# controller.net
KiCad netlist of a schematic drawn in EAGLE
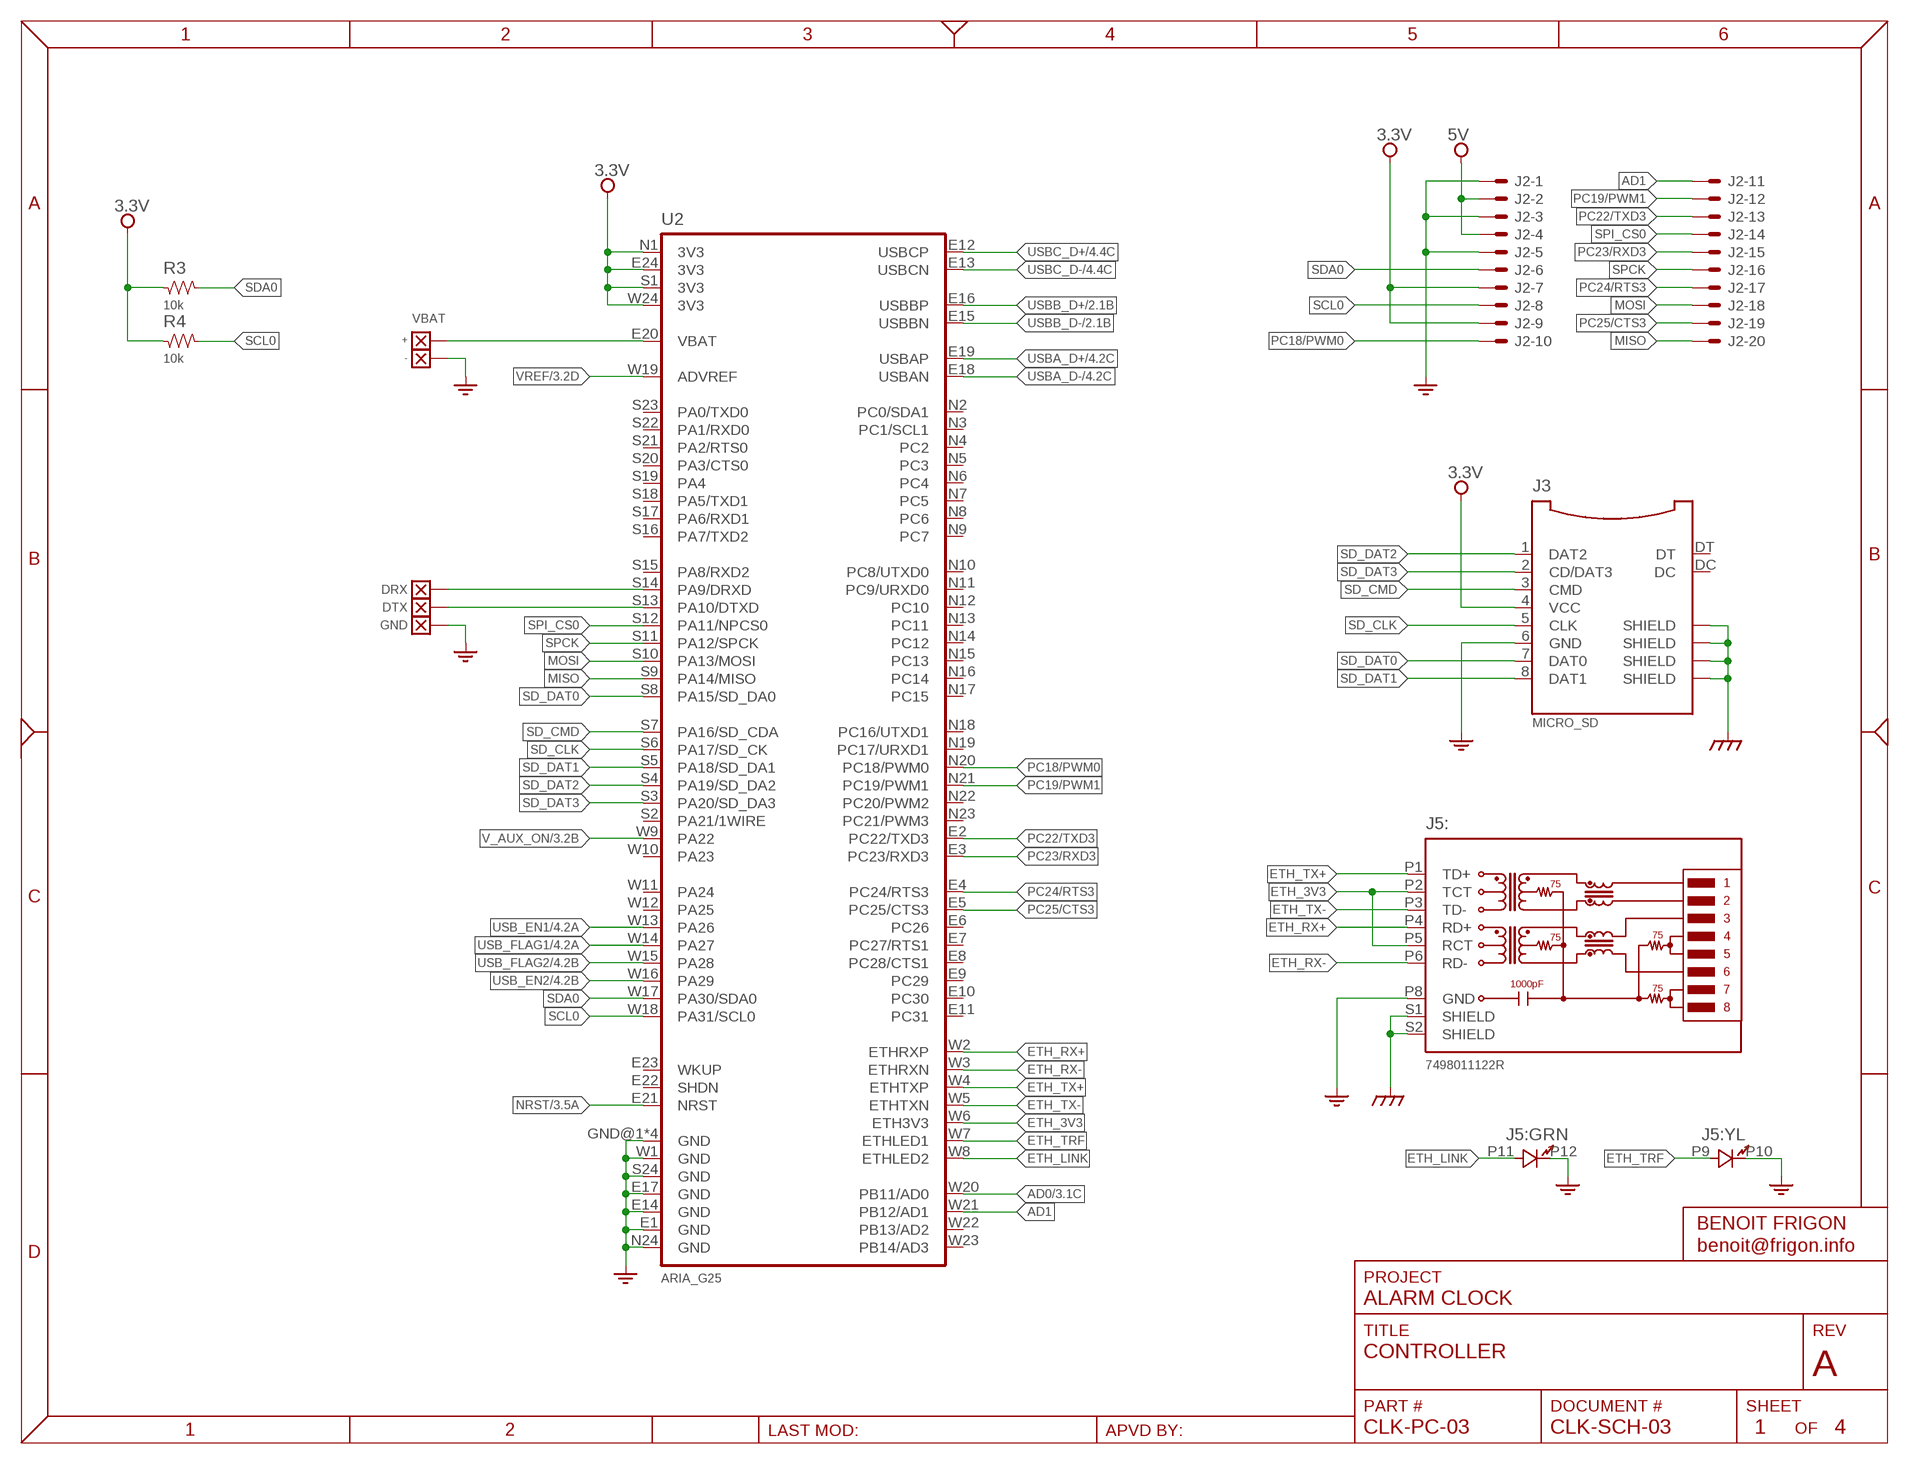
[diagram p0: schematic, sheet 1]
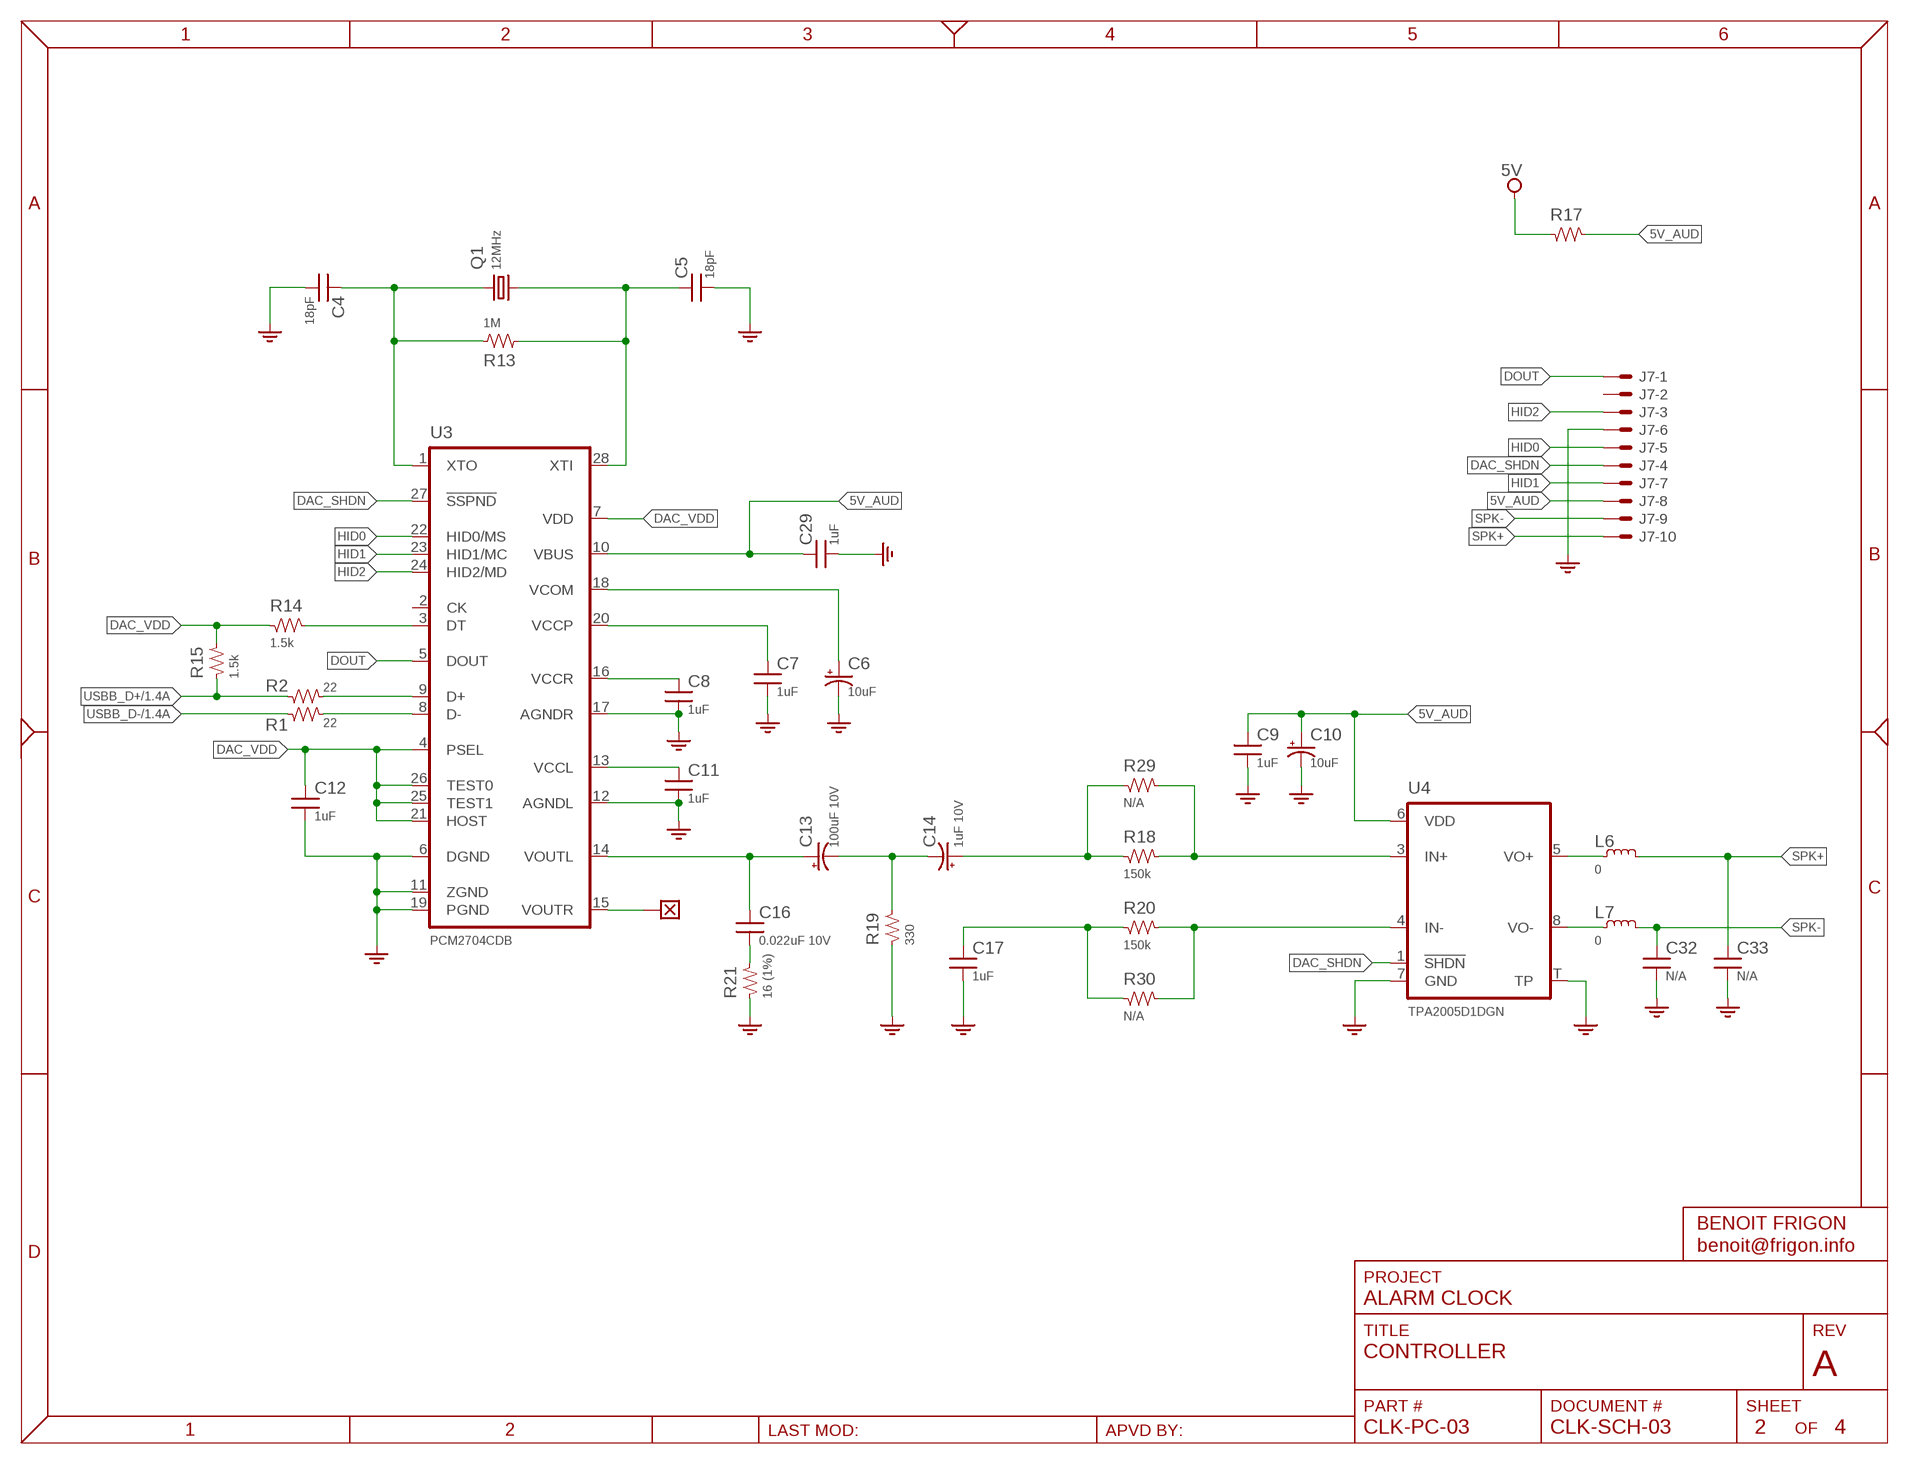
[diagram p1: schematic, sheet 2]
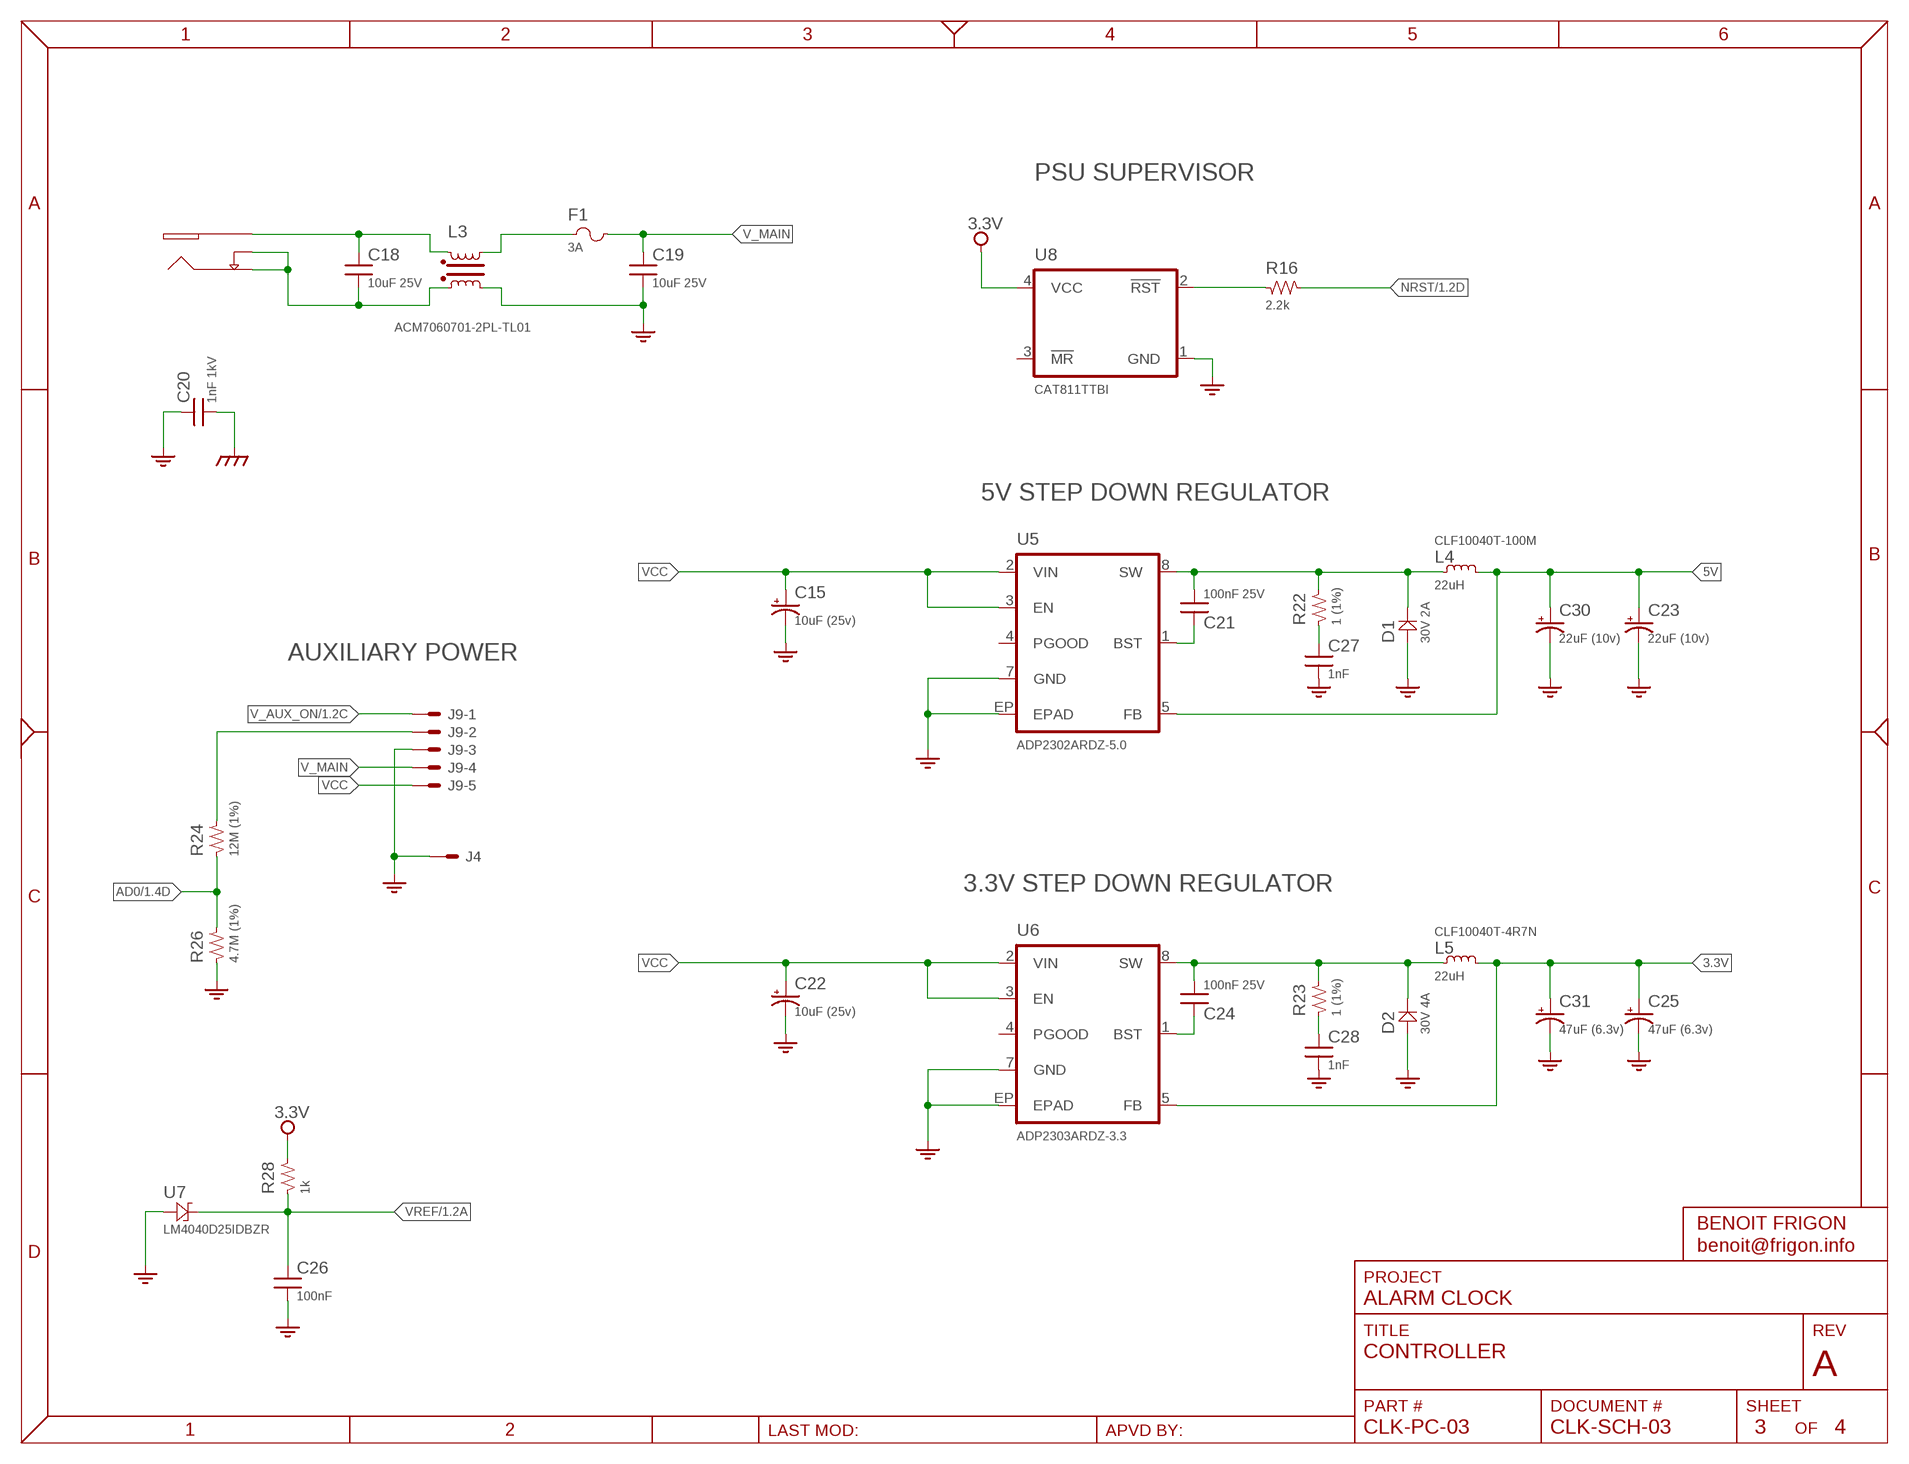
[diagram p2: schematic, sheet 3]
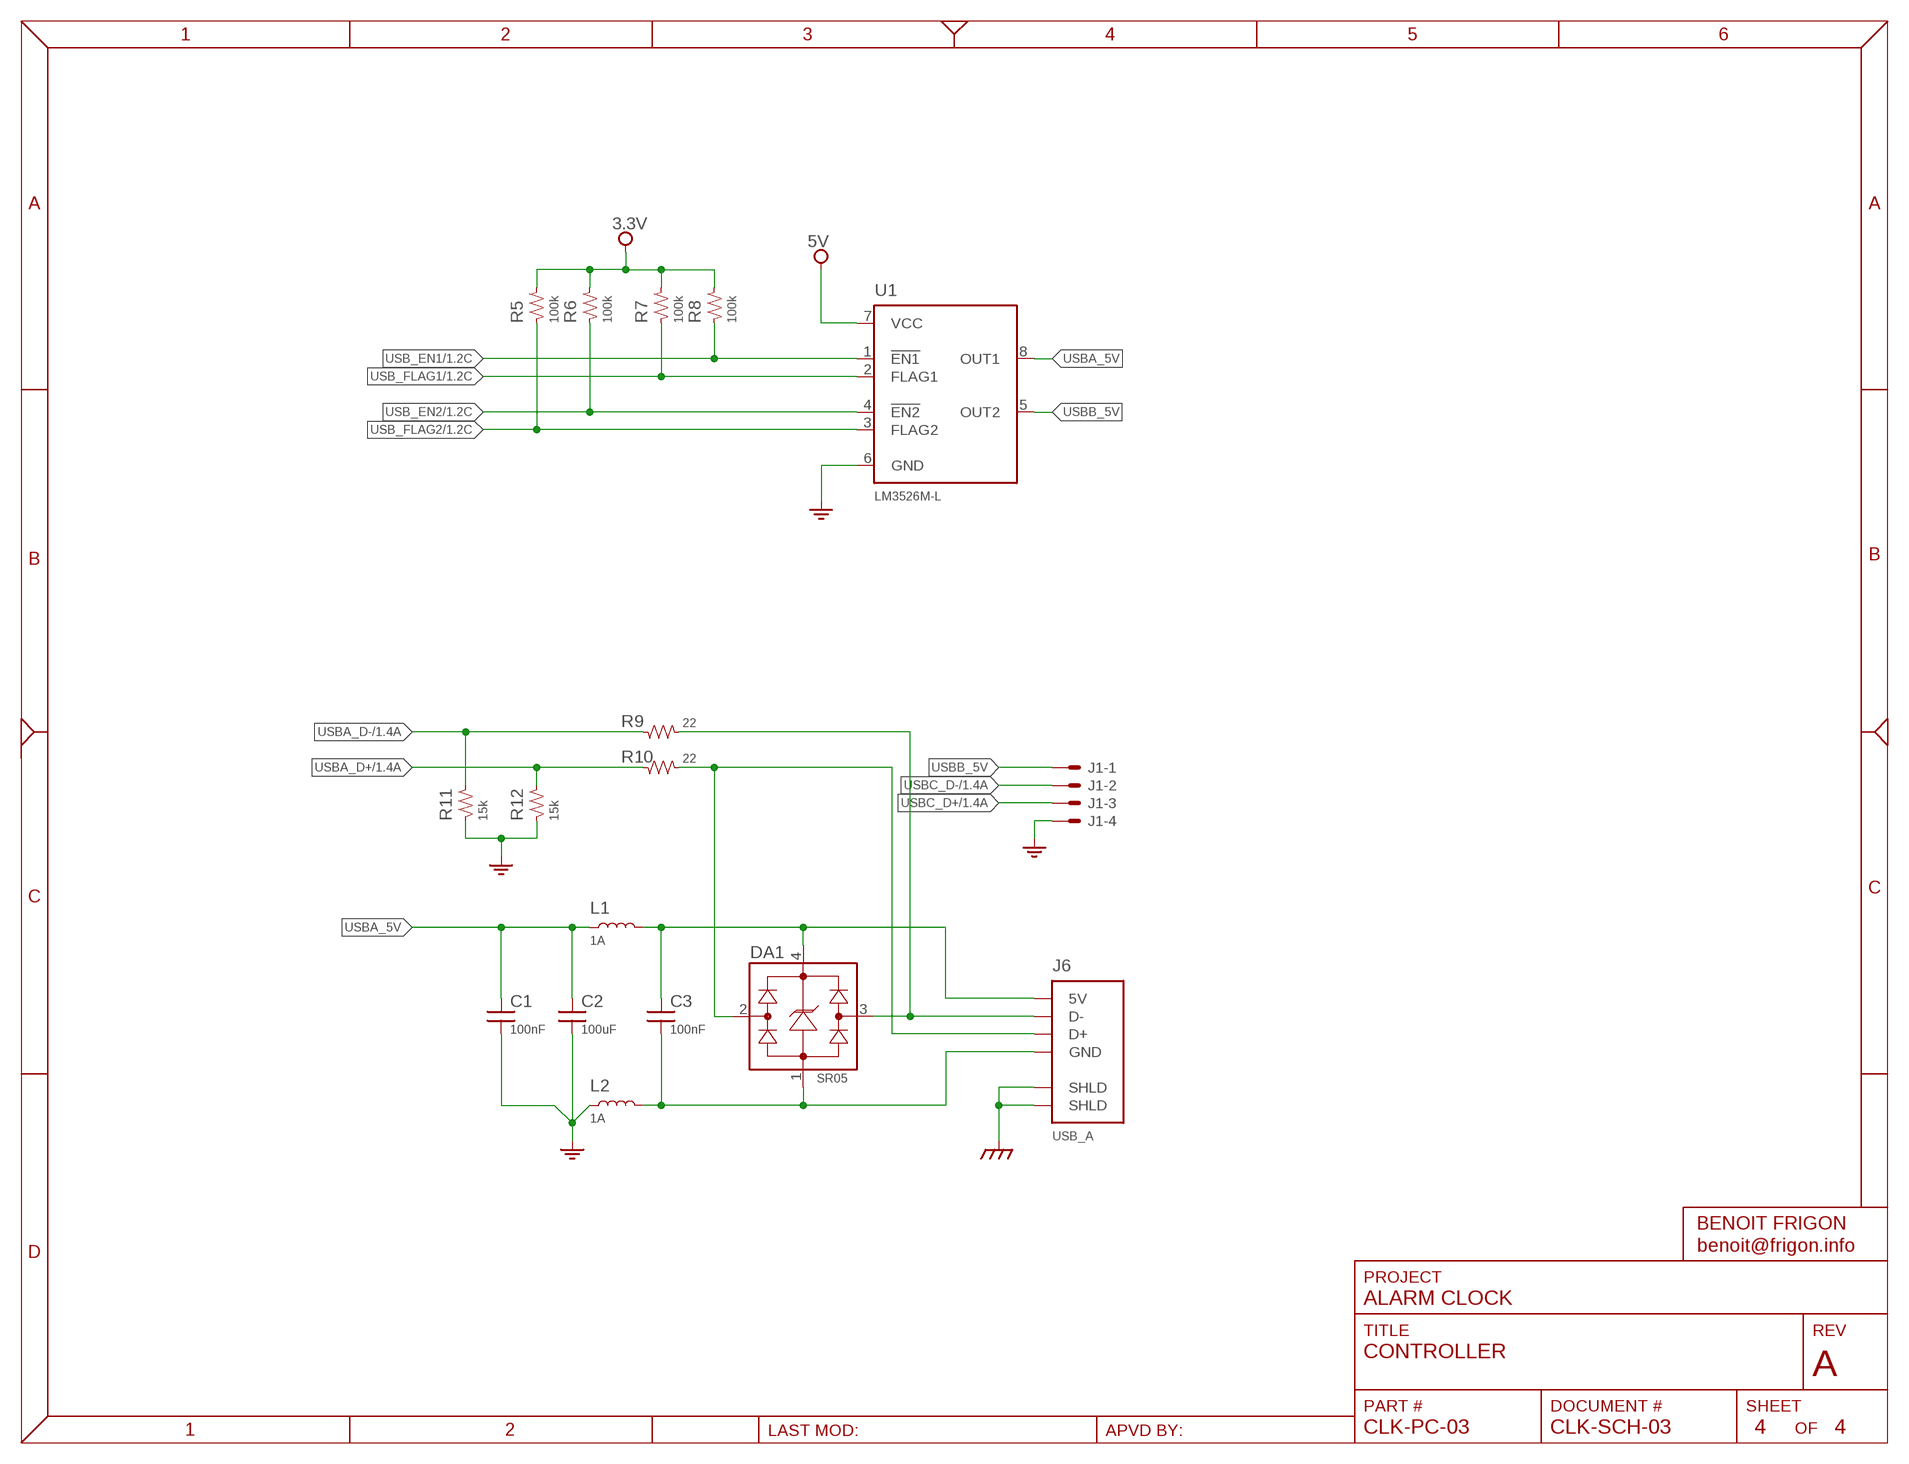
[diagram p3: schematic, sheet 4]

(export (version "E")
  (design (tool "Eeschema 10.0.6"))
  (components
    (comp (ref "C15")
      (value "10uF (25v)")
      (footprint "eagle-import:CAP_S1210")
      (fields (field (name "MFG") "AVX") (field (name "PART_NO") "TPSB106K025R1800"))
      (libsource (lib "eagle-import") (part "CAP-E-?-1210TANT"))
    )
    (comp (ref "C18")
      (value "10uF 25V")
      (footprint "eagle-import:SMD_1206")
      (description "{DESCRIPTION} - SMT 1206 - {value}")
      (fields (field (name "PACKAGE") "SMT 1206"))
      (libsource (lib "eagle-import") (part "CAP-1206"))
    )
    (comp (ref "C19")
      (value "10uF 25V")
      (footprint "eagle-import:SMD_1206")
      (description "{DESCRIPTION} - SMT 1206 - {value}")
      (fields (field (name "PACKAGE") "SMT 1206"))
      (libsource (lib "eagle-import") (part "CAP-1206"))
    )
    (comp (ref "C20")
      (value "1nF 1kV")
      (footprint "eagle-import:SMD_0805")
      (libsource (lib "eagle-import") (part "CAP-0805"))
    )
    (comp (ref "C21")
      (value "100nF 25V")
      (footprint "eagle-import:SMD_0603")
      (libsource (lib "eagle-import") (part "CAP-0603"))
    )
    (comp (ref "C22")
      (value "10uF (25v)")
      (footprint "eagle-import:CAP_S1210")
      (fields (field (name "MFG") "AVX") (field (name "PART_NO") "TPSB106K025R1800"))
      (libsource (lib "eagle-import") (part "CAP-E-?-1210TANT"))
    )
    (comp (ref "C23")
      (value "22uF (10v)")
      (footprint "eagle-import:CAP_S1206")
      (description "Tantalum capacitor - SMT 1206 - {VALUE}")
      (fields (field (name "MFG") "AVX") (field (name "PART_NO") "TPSA226M010R0900"))
      (libsource (lib "eagle-import") (part "CAP-E-?-1206TANT"))
    )
    (comp (ref "C24")
      (value "100nF 25V")
      (footprint "eagle-import:SMD_0603")
      (libsource (lib "eagle-import") (part "CAP-0603"))
    )
    (comp (ref "C25")
      (value "47uF (6.3v)")
      (footprint "eagle-import:CAP_S1206")
      (description "Tantalum capacitor - SMT 1206 - {VALUE}")
      (fields (field (name "MFG") "AVX") (field (name "PART_NO") "TPSA476K006R0800"))
      (libsource (lib "eagle-import") (part "CAP-E-?-1206TANT"))
    )
    (comp (ref "C26")
      (value "100nF")
      (footprint "eagle-import:SMD_0603")
      (libsource (lib "eagle-import") (part "CAP-0603"))
    )
    (comp (ref "C27")
      (value "1nF")
      (footprint "eagle-import:SMD_0805")
      (libsource (lib "eagle-import") (part "CAP-0805"))
    )
    (comp (ref "C28")
      (value "1nF")
      (footprint "eagle-import:SMD_0805")
      (description "{DESCRIPTION} - SMT 0805 - {value}")
      (fields (field (name "PACKAGE") "SMT 0805"))
      (libsource (lib "eagle-import") (part "CAP-0805"))
    )
    (comp (ref "C30")
      (value "22uF (10v)")
      (footprint "eagle-import:CAP_S1206")
      (description "Tantalum capacitor - SMT 1206 - {VALUE}")
      (fields (field (name "MFG") "AVX") (field (name "PART_NO") "TPSA226M010R0900"))
      (libsource (lib "eagle-import") (part "CAP-E-?-1206TANT"))
    )
    (comp (ref "C31")
      (value "47uF (6.3v)")
      (footprint "eagle-import:CAP_S1206")
      (description "Tantalum capacitor - SMT 1206 - {VALUE}")
      (fields (field (name "MFG") "AVX") (field (name "PART_NO") "TPSA476K006R0800"))
      (libsource (lib "eagle-import") (part "CAP-E-?-1206TANT"))
    )
    (comp (ref "D1")
      (value "30V 2A")
      (footprint "eagle-import:DIODE_DO214-AA")
      (libsource (lib "eagle-import") (part "DIODE-DO214-AA"))
    )
    (comp (ref "D2")
      (value "30V 4A")
      (footprint "eagle-import:DIODE_DO214-AA")
      (libsource (lib "eagle-import") (part "DIODE-DO214-AA"))
    )
    (comp (ref "F1")
      (value "3A")
      (footprint "eagle-import:SMD_1206")
      (libsource (lib "eagle-import") (part "FUSE1206"))
    )
    (comp (ref "J4")
      (value "SNG-100-HEADER-01-HDR-V")
      (footprint "eagle-import:HDR_M_1")
      (libsource (lib "eagle-import") (part "SNG-100-HEADER-01-HDR-V"))
    )
    (comp (ref "J8")
      (value "CUI-PJ-013C")
      (footprint "eagle-import:CUI-PJ-013C")
      (libsource (lib "eagle-import") (part "CUI-PJ-013C"))
    )
    (comp (ref "J9")
      (value "SNG-100-HEADER-05-HDR-V")
      (footprint "eagle-import:HDR_M_5")
      (libsource (lib "eagle-import") (part "SNG-100-HEADER-05-HDR-V"))
    )
    (comp (ref "L3")
      (value "ACM7060701-2PL-TL01")
      (footprint "eagle-import:ACM7060")
      (libsource (lib "eagle-import") (part "CHOKE-?ACM7060701-2PL-TL01"))
    )
    (comp (ref "L4")
      (value "22uH")
      (footprint "eagle-import:IND-10X10")
      (fields (field (name "MFG") "TDK") (field (name "PART_NO") "CLF10040T-100M"))
      (libsource (lib "eagle-import") (part "IND?-10X10"))
    )
    (comp (ref "L5")
      (value "22uH")
      (footprint "eagle-import:IND-10X10")
      (fields (field (name "PART_NO") "CLF10040T-4R7N"))
      (libsource (lib "eagle-import") (part "IND?-10X10"))
    )
    (comp (ref "R16")
      (value "2.2k")
      (footprint "eagle-import:SMD_0603")
      (libsource (lib "eagle-import") (part "RES-0603"))
    )
    (comp (ref "R22")
      (value "1 (1%)")
      (footprint "eagle-import:SMD_0805")
      (libsource (lib "eagle-import") (part "RES-0805"))
    )
    (comp (ref "R23")
      (value "1 (1%)")
      (footprint "eagle-import:SMD_0805")
      (description "{DESCRIPTION} - SMT 0805 - {VALUE}")
      (fields (field (name "PACKAGE") "SMT 0805"))
      (libsource (lib "eagle-import") (part "RES-0805"))
    )
    (comp (ref "R24")
      (value "12M (1%)")
      (footprint "eagle-import:SMD_0603")
      (libsource (lib "eagle-import") (part "RES-0603"))
    )
    (comp (ref "R26")
      (value "4.7M (1%)")
      (footprint "eagle-import:SMD_0603")
      (libsource (lib "eagle-import") (part "RES-0603"))
    )
    (comp (ref "R28")
      (value "1k")
      (footprint "eagle-import:SMD_0603")
      (libsource (lib "eagle-import") (part "RES-0603"))
    )
    (comp (ref "U5")
      (value "ADP2302ARDZ-5.0")
      (footprint "eagle-import:SOIC8-EP")
      (description "{DESCRIPTION} - 2A, 5V")
      (fields (field (name "MFG") "Analog Devices"))
      (libsource (lib "eagle-import") (part "ADP230?2ARDZ-5.0"))
    )
    (comp (ref "U6")
      (value "ADP2303ARDZ-3.3")
      (footprint "eagle-import:SOIC8-EP")
      (description "{DESCRIPTION} - 3A, 3.3v")
      (fields (field (name "MFG") "Analog Devices"))
      (libsource (lib "eagle-import") (part "ADP230?3ARDZ-3.3"))
    )
    (comp (ref "U7")
      (value "LM4040D25IDBZR")
      (footprint "eagle-import:SOT23")
      (libsource (lib "eagle-import") (part "TS4040DBZD30I"))
    )
    (comp (ref "U8")
      (value "CAT811TTBI")
      (footprint "eagle-import:SOT143")
      (description "{DESCRIPTION} - 3.08V threshold")
      (fields (field (name "MFG") "ON Semiconductors"))
      (libsource (lib "eagle-import") (part "CAT811?TBIT"))
    )
    (comp (ref "C4")
      (value "18pF")
      (footprint "eagle-import:SMD_0603")
      (description "{DESCRIPTION} - SMT 0603 - {value}")
      (fields (field (name "PACKAGE") "SMT 0603"))
      (libsource (lib "eagle-import") (part "CAP-0603"))
    )
    (comp (ref "C5")
      (value "18pF")
      (footprint "eagle-import:SMD_0603")
      (libsource (lib "eagle-import") (part "CAP-0603"))
    )
    (comp (ref "C6")
      (value "10uF")
      (footprint "eagle-import:CAP_S0805")
      (description "Aluminium capacitor - SMT 0805 - {VALUE}")
      (libsource (lib "eagle-import") (part "CAP-E-?-0805ALUM"))
    )
    (comp (ref "C7")
      (value "1uF")
      (footprint "eagle-import:SMD_0603")
      (libsource (lib "eagle-import") (part "CAP-0603"))
    )
    (comp (ref "C8")
      (value "1uF")
      (footprint "eagle-import:SMD_0603")
      (description "{DESCRIPTION} - SMT 0603 - {value}")
      (fields (field (name "PACKAGE") "SMT 0603"))
      (libsource (lib "eagle-import") (part "CAP-0603"))
    )
    (comp (ref "C9")
      (value "1uF")
      (footprint "eagle-import:SMD_0603")
      (libsource (lib "eagle-import") (part "CAP-0603"))
    )
    (comp (ref "C10")
      (value "10uF")
      (footprint "eagle-import:CAP_S0805")
      (description "Aluminium capacitor - SMT 0805 - {VALUE}")
      (libsource (lib "eagle-import") (part "CAP-E-?-0805ALUM"))
    )
    (comp (ref "C11")
      (value "1uF")
      (footprint "eagle-import:SMD_0603")
      (description "{DESCRIPTION} - SMT 0603 - {value}")
      (fields (field (name "PACKAGE") "SMT 0603"))
      (libsource (lib "eagle-import") (part "CAP-0603"))
    )
    (comp (ref "C12")
      (value "1uF")
      (footprint "eagle-import:SMD_0603")
      (libsource (lib "eagle-import") (part "CAP-0603"))
    )
    (comp (ref "C13")
      (value "100uF 10V")
      (footprint "eagle-import:CAP_S1210")
      (description "Aluminium capacitor - SMT 1210 - {VALUE}")
      (fields (field (name "MFG") "AVX"))
      (libsource (lib "eagle-import") (part "CAP-E-?-1210ALUM"))
    )
    (comp (ref "C14")
      (value "1uF 10V")
      (footprint "eagle-import:CAP_S0805")
      (description "Aluminium capacitor - SMT 0805 - {VALUE}")
      (libsource (lib "eagle-import") (part "CAP-E-?-0805ALUM"))
    )
    (comp (ref "C16")
      (value "0.022uF 10V")
      (footprint "eagle-import:SMD_0603")
      (libsource (lib "eagle-import") (part "CAP-0603"))
    )
    (comp (ref "C17")
      (value "1uF")
      (footprint "eagle-import:SMD_0603")
      (libsource (lib "eagle-import") (part "CAP-0603"))
    )
    (comp (ref "C29")
      (value "1uF")
      (footprint "eagle-import:SMD_0603")
      (libsource (lib "eagle-import") (part "CAP-0603"))
    )
    (comp (ref "C32")
      (value "N/A")
      (footprint "eagle-import:SMD_0603")
      (libsource (lib "eagle-import") (part "CAP-0603"))
    )
    (comp (ref "C33")
      (value "N/A")
      (footprint "eagle-import:SMD_0603")
      (libsource (lib "eagle-import") (part "CAP-0603"))
    )
    (comp (ref "J7")
      (value "DL-1.25MM-HEADER-10")
      (footprint "eagle-import:DF13A-10DP-1.25")
      (libsource (lib "eagle-import") (part "DL-1.25MM-HEADER-10"))
    )
    (comp (ref "L6")
      (value "0")
      (footprint "eagle-import:SMD_0603")
      (description "{DESCRIPTION} - SMT 0603 - {VALUE}")
      (libsource (lib "eagle-import") (part "IND?-0603"))
    )
    (comp (ref "L7")
      (value "0")
      (footprint "eagle-import:SMD_0603")
      (description "{DESCRIPTION} - SMT 0603 - {VALUE}")
      (libsource (lib "eagle-import") (part "IND?-0603"))
    )
    (comp (ref "Q1")
      (value "12MHz")
      (footprint "eagle-import:HC49UP")
      (libsource (lib "eagle-import") (part "XTALHC49UP"))
    )
    (comp (ref "R1")
      (value "22")
      (footprint "eagle-import:SMD_0603")
      (libsource (lib "eagle-import") (part "RES-0603"))
    )
    (comp (ref "R2")
      (value "22")
      (footprint "eagle-import:SMD_0603")
      (libsource (lib "eagle-import") (part "RES-0603"))
    )
    (comp (ref "R13")
      (value "1M")
      (footprint "eagle-import:SMD_0603")
      (libsource (lib "eagle-import") (part "RES-0603"))
    )
    (comp (ref "R14")
      (value "1.5k")
      (footprint "eagle-import:SMD_0603")
      (libsource (lib "eagle-import") (part "RES-0603"))
    )
    (comp (ref "R15")
      (value "1.5k")
      (footprint "eagle-import:SMD_0603")
      (libsource (lib "eagle-import") (part "RES-0603"))
    )
    (comp (ref "R17")
      (value "RES-1206")
      (footprint "eagle-import:SMD_1206")
      (libsource (lib "eagle-import") (part "RES-1206"))
    )
    (comp (ref "R18")
      (value "150k")
      (footprint "eagle-import:SMD_0603")
      (libsource (lib "eagle-import") (part "RES-0603"))
    )
    (comp (ref "R19")
      (value "330")
      (footprint "eagle-import:SMD_0603")
      (libsource (lib "eagle-import") (part "RES-0603"))
    )
    (comp (ref "R20")
      (value "150k")
      (footprint "eagle-import:SMD_0603")
      (description "{DESCRIPTION} - SMT 0603 - {VALUE}")
      (fields (field (name "PACKAGE") "SMT 0603"))
      (libsource (lib "eagle-import") (part "RES-0603"))
    )
    (comp (ref "R21")
      (value "16 (1%)")
      (footprint "eagle-import:SMD_0603")
      (libsource (lib "eagle-import") (part "RES-0603"))
    )
    (comp (ref "R29")
      (value "N/A")
      (footprint "eagle-import:SMD_0603")
      (description "{DESCRIPTION} - SMT 0603 - {VALUE}")
      (fields (field (name "PACKAGE") "SMT 0603"))
      (libsource (lib "eagle-import") (part "RES-0603"))
    )
    (comp (ref "R30")
      (value "N/A")
      (footprint "eagle-import:SMD_0603")
      (description "{DESCRIPTION} - SMT 0603 - {VALUE}")
      (fields (field (name "PACKAGE") "SMT 0603"))
      (libsource (lib "eagle-import") (part "RES-0603"))
    )
    (comp (ref "U3")
      (value "PCM2704CDB")
      (footprint "eagle-import:SSOP28")
      (libsource (lib "eagle-import") (part "PCM2704CDB"))
    )
    (comp (ref "U4")
      (value "TPA2005D1DGN")
      (footprint "eagle-import:PPSOP8")
      (libsource (lib "eagle-import") (part "TPA2005D1?DGN"))
    )
    (comp (ref "W1")
      (value "WIRE-150X75")
      (footprint "eagle-import:WIRE_SMT_150X75")
      (libsource (lib "eagle-import") (part "WIRE-?150X75"))
    )
    (comp (ref "J2")
      (value "DL-1.25MM-HEADER-20")
      (footprint "eagle-import:DF13A-20DP-1.25")
      (libsource (lib "eagle-import") (part "DL-1.25MM-HEADER-20"))
    )
    (comp (ref "J3")
      (value "MICRO_SD")
      (footprint "eagle-import:5027020891")
      (libsource (lib "eagle-import") (part "MICRO_SD"))
    )
    (comp (ref "J5")
      (value "7498011122R")
      (footprint "eagle-import:7498011122R")
      (libsource (lib "eagle-import") (part "7498011122R"))
    )
    (comp (ref "R3")
      (value "10k")
      (footprint "eagle-import:SMD_0603")
      (description "{DESCRIPTION} - SMT 0603 - {VALUE}")
      (fields (field (name "PACKAGE") "SMT 0603"))
      (libsource (lib "eagle-import") (part "RES-0603"))
    )
    (comp (ref "R4")
      (value "10k")
      (footprint "eagle-import:SMD_0603")
      (description "{DESCRIPTION} - SMT 0603 - {VALUE}")
      (fields (field (name "PACKAGE") "SMT 0603"))
      (libsource (lib "eagle-import") (part "RES-0603"))
    )
    (comp (ref "TP1")
      (value "+")
      (footprint "eagle-import:WIRE_SMT_150X75")
      (libsource (lib "eagle-import") (part "WIRE-?150X75"))
    )
    (comp (ref "TP2")
      (value "-")
      (footprint "eagle-import:WIRE_SMT_150X75")
      (libsource (lib "eagle-import") (part "WIRE-?150X75"))
    )
    (comp (ref "U2")
      (value "ARIA_G25")
      (footprint "eagle-import:ARIA_G25")
      (libsource (lib "eagle-import") (part "ARIA_G25"))
    )
    (comp (ref "W2")
      (value "DRX")
      (footprint "eagle-import:WIRE_SMT_150X75")
      (libsource (lib "eagle-import") (part "WIRE-?150X75"))
    )
    (comp (ref "W3")
      (value "DTX")
      (footprint "eagle-import:WIRE_SMT_150X75")
      (libsource (lib "eagle-import") (part "WIRE-?150X75"))
    )
    (comp (ref "W4")
      (value "GND")
      (footprint "eagle-import:WIRE_SMT_150X75")
      (libsource (lib "eagle-import") (part "WIRE-?150X75"))
    )
    (comp (ref "C1")
      (value "100nF")
      (footprint "eagle-import:SMD_0603")
      (libsource (lib "eagle-import") (part "CAP-0603"))
    )
    (comp (ref "C2")
      (value "100uF")
      (footprint "eagle-import:SMD_0805")
      (libsource (lib "eagle-import") (part "CAP-0805"))
    )
    (comp (ref "C3")
      (value "100nF")
      (footprint "eagle-import:SMD_0603")
      (libsource (lib "eagle-import") (part "CAP-0603"))
    )
    (comp (ref "DA1")
      (value "SR05")
      (footprint "eagle-import:SOT143")
      (fields (field (name "MFG") "Semtech"))
      (libsource (lib "eagle-import") (part "SR05"))
    )
    (comp (ref "J1")
      (value "SNG-2MM-HEADER-04-V")
      (footprint "eagle-import:DF3X-4P-2DSA")
      (description "{DESCRIPTION} - Vertical")
      (fields (field (name "MFG") "Hirose Electronic") (field (name "SKU") "DF3A-4P-2DSA"))
      (libsource (lib "eagle-import") (part "SNG-2MM-HEADER-04-V"))
    )
    (comp (ref "J6")
      (value "USB_A")
      (footprint "eagle-import:292303-7")
      (libsource (lib "eagle-import") (part "USB_A"))
    )
    (comp (ref "L1")
      (value "1A")
      (footprint "eagle-import:SMD_0805")
      (libsource (lib "eagle-import") (part "FERRITE"))
    )
    (comp (ref "L2")
      (value "1A")
      (footprint "eagle-import:SMD_0805")
      (description "{DESCRIPTION} - SMT 0805 - {VALUE}")
      (libsource (lib "eagle-import") (part "FERRITE"))
    )
    (comp (ref "R5")
      (value "100k")
      (footprint "eagle-import:SMD_0603")
      (description "{DESCRIPTION} - SMT 0603 - {VALUE}")
      (fields (field (name "PACKAGE") "SMT 0603"))
      (libsource (lib "eagle-import") (part "RES-0603"))
    )
    (comp (ref "R6")
      (value "100k")
      (footprint "eagle-import:SMD_0603")
      (description "{DESCRIPTION} - SMT 0603 - {VALUE}")
      (fields (field (name "PACKAGE") "SMT 0603"))
      (libsource (lib "eagle-import") (part "RES-0603"))
    )
    (comp (ref "R7")
      (value "100k")
      (footprint "eagle-import:SMD_0603")
      (description "{DESCRIPTION} - SMT 0603 - {VALUE}")
      (fields (field (name "PACKAGE") "SMT 0603"))
      (libsource (lib "eagle-import") (part "RES-0603"))
    )
    (comp (ref "R8")
      (value "100k")
      (footprint "eagle-import:SMD_0603")
      (description "{DESCRIPTION} - SMT 0603 - {VALUE}")
      (fields (field (name "PACKAGE") "SMT 0603"))
      (libsource (lib "eagle-import") (part "RES-0603"))
    )
    (comp (ref "R9")
      (value "22")
      (footprint "eagle-import:SMD_0603")
      (description "{DESCRIPTION} - SMT 0603 - {VALUE}")
      (fields (field (name "PACKAGE") "SMT 0603"))
      (libsource (lib "eagle-import") (part "RES-0603"))
    )
    (comp (ref "R10")
      (value "22")
      (footprint "eagle-import:SMD_0603")
      (description "{DESCRIPTION} - SMT 0603 - {VALUE}")
      (fields (field (name "PACKAGE") "SMT 0603"))
      (libsource (lib "eagle-import") (part "RES-0603"))
    )
    (comp (ref "R11")
      (value "15k")
      (footprint "eagle-import:SMD_0603")
      (description "{DESCRIPTION} - SMT 0603 - {VALUE}")
      (fields (field (name "PACKAGE") "SMT 0603"))
      (libsource (lib "eagle-import") (part "RES-0603"))
    )
    (comp (ref "R12")
      (value "15k")
      (footprint "eagle-import:SMD_0603")
      (description "{DESCRIPTION} - SMT 0603 - {VALUE}")
      (fields (field (name "PACKAGE") "SMT 0603"))
      (libsource (lib "eagle-import") (part "RES-0603"))
    )
    (comp (ref "U1")
      (value "LM3526M-L")
      (footprint "eagle-import:SOIC8")
      (fields (field (name "MFG") "National Semiconductors"))
      (libsource (lib "eagle-import") (part "LM3526?-ML"))
    )
  )
  (nets
    (net (code "1") (name "3.3V") (class "Default")
      (node (ref "C25") (pin "+") (pinfunction "+_+") (pintype "passive"))
      (node (ref "C31") (pin "+") (pinfunction "+_+") (pintype "passive"))
      (node (ref "J2") (pin "7") (pinfunction "S_7") (pintype "bidirectional"))
      (node (ref "J2") (pin "9") (pinfunction "S_9") (pintype "bidirectional"))
      (node (ref "J3") (pin "4") (pinfunction "VCC_4") (pintype "power_in"))
      (node (ref "L5") (pin "2") (pinfunction "2_2") (pintype "passive"))
      (node (ref "R28") (pin "2") (pinfunction "2_2") (pintype "passive"))
      (node (ref "R3") (pin "1") (pinfunction "1_1") (pintype "passive"))
      (node (ref "R4") (pin "1") (pinfunction "1_1") (pintype "passive"))
      (node (ref "R5") (pin "2") (pinfunction "2_2") (pintype "passive"))
      (node (ref "R6") (pin "2") (pinfunction "2_2") (pintype "passive"))
      (node (ref "R7") (pin "2") (pinfunction "2_2") (pintype "passive"))
      (node (ref "R8") (pin "2") (pinfunction "2_2") (pintype "passive"))
      (node (ref "U2") (pin "E24") (pinfunction "3V3_E24") (pintype "power_in"))
      (node (ref "U2") (pin "N1") (pinfunction "3V3_N1") (pintype "power_in"))
      (node (ref "U2") (pin "S1") (pinfunction "3V3_S1") (pintype "power_in"))
      (node (ref "U2") (pin "W24") (pinfunction "3V3_W24") (pintype "power_in"))
      (node (ref "U6") (pin "5") (pinfunction "FB_5") (pintype "bidirectional"))
      (node (ref "U8") (pin "4") (pinfunction "VCC_4") (pintype "power_in"))
    )
    (net (code "2") (name "5V") (class "Default")
      (node (ref "C23") (pin "+") (pinfunction "+_+") (pintype "passive"))
      (node (ref "C30") (pin "+") (pinfunction "+_+") (pintype "passive"))
      (node (ref "J2") (pin "2") (pinfunction "S_2") (pintype "bidirectional"))
      (node (ref "J2") (pin "4") (pinfunction "S_4") (pintype "bidirectional"))
      (node (ref "L4") (pin "2") (pinfunction "2_2") (pintype "passive"))
      (node (ref "R17") (pin "1") (pinfunction "1_1") (pintype "passive"))
      (node (ref "U1") (pin "7") (pinfunction "VCC_7") (pintype "bidirectional"))
      (node (ref "U5") (pin "5") (pinfunction "FB_5") (pintype "bidirectional"))
    )
    (net (code "3") (name "5V_AUD") (class "Default")
      (node (ref "C10") (pin "+") (pinfunction "+_+") (pintype "passive"))
      (node (ref "C29") (pin "1") (pinfunction "1_1") (pintype "passive"))
      (node (ref "C9") (pin "1") (pinfunction "1_1") (pintype "passive"))
      (node (ref "J7") (pin "8") (pinfunction "S_8") (pintype "bidirectional"))
      (node (ref "R17") (pin "2") (pinfunction "2_2") (pintype "passive"))
      (node (ref "U3") (pin "10") (pinfunction "VBUS_10") (pintype "bidirectional"))
      (node (ref "U4") (pin "6") (pinfunction "VDD_6") (pintype "bidirectional"))
    )
    (net (code "4") (name "AD0") (class "Default")
      (node (ref "R24") (pin "1") (pinfunction "1_1") (pintype "passive"))
      (node (ref "R26") (pin "2") (pinfunction "2_2") (pintype "passive"))
      (node (ref "U2") (pin "W20") (pinfunction "PB11/AD0_W20") (pintype "bidirectional"))
    )
    (net (code "5") (name "AD1") (class "Default")
      (node (ref "J2") (pin "11") (pinfunction "S_11") (pintype "bidirectional"))
      (node (ref "U2") (pin "W21") (pinfunction "PB12/AD1_W21") (pintype "bidirectional"))
    )
    (net (code "6") (name "DAC_SHDN") (class "Default")
      (node (ref "J7") (pin "4") (pinfunction "S_4") (pintype "bidirectional"))
      (node (ref "U3") (pin "27") (pinfunction "~{SSPND}_27") (pintype "bidirectional"))
      (node (ref "U4") (pin "1") (pinfunction "~{SHDN}_1") (pintype "bidirectional"))
    )
    (net (code "7") (name "DAC_VDD") (class "Default")
      (node (ref "C12") (pin "1") (pinfunction "1_1") (pintype "passive"))
      (node (ref "R14") (pin "1") (pinfunction "1_1") (pintype "passive"))
      (node (ref "R15") (pin "2") (pinfunction "2_2") (pintype "passive"))
      (node (ref "U3") (pin "21") (pinfunction "HOST_21") (pintype "bidirectional"))
      (node (ref "U3") (pin "25") (pinfunction "TEST1_25") (pintype "bidirectional"))
      (node (ref "U3") (pin "26") (pinfunction "TEST0_26") (pintype "bidirectional"))
      (node (ref "U3") (pin "4") (pinfunction "PSEL_4") (pintype "bidirectional"))
      (node (ref "U3") (pin "7") (pinfunction "VDD_7") (pintype "bidirectional"))
    )
    (net (code "8") (name "DOUT") (class "Default")
      (node (ref "J7") (pin "1") (pinfunction "S_1") (pintype "bidirectional"))
      (node (ref "U3") (pin "5") (pinfunction "DOUT_5") (pintype "bidirectional"))
    )
    (net (code "9") (name "EARTH") (class "Default")
      (node (ref "C20") (pin "2") (pinfunction "2_2") (pintype "passive"))
      (node (ref "J3") (pin "SHDL@3") (pinfunction "SHIELD_SHDL@3") (pintype "power_in"))
      (node (ref "J3") (pin "SHLD@1") (pinfunction "SHIELD_SHLD@1") (pintype "power_in"))
      (node (ref "J3") (pin "SHLD@2") (pinfunction "SHIELD_SHLD@2") (pintype "power_in"))
      (node (ref "J3") (pin "SHLD@4") (pinfunction "SHIELD_SHLD@4") (pintype "power_in"))
      (node (ref "J5") (pin "S1") (pinfunction "SHIELD_S1") (pintype "bidirectional"))
      (node (ref "J5") (pin "S2") (pinfunction "SHIELD_S2") (pintype "bidirectional"))
      (node (ref "J6") (pin "SHLD@1") (pinfunction "SHLD_SHLD@1") (pintype "bidirectional"))
      (node (ref "J6") (pin "SHLD@2") (pinfunction "SHLD_SHLD@2") (pintype "bidirectional"))
    )
    (net (code "10") (name "ETH_3V3") (class "Default")
      (node (ref "J5") (pin "P2") (pinfunction "TCT_P2") (pintype "bidirectional"))
      (node (ref "J5") (pin "P5") (pinfunction "RCT_P5") (pintype "bidirectional"))
      (node (ref "U2") (pin "W6") (pinfunction "ETH3V3_W6") (pintype "bidirectional"))
    )
    (net (code "11") (name "ETH_LINK") (class "Default")
      (node (ref "J5") (pin "P11") (pinfunction "A_P11") (pintype "bidirectional"))
      (node (ref "U2") (pin "W8") (pinfunction "ETHLED2_W8") (pintype "bidirectional"))
    )
    (net (code "12") (name "ETH_RX+") (class "Default")
      (node (ref "J5") (pin "P4") (pinfunction "RD+_P4") (pintype "bidirectional"))
      (node (ref "U2") (pin "W2") (pinfunction "ETHRXP_W2") (pintype "bidirectional"))
    )
    (net (code "13") (name "ETH_RX-") (class "Default")
      (node (ref "J5") (pin "P6") (pinfunction "RD-_P6") (pintype "bidirectional"))
      (node (ref "U2") (pin "W3") (pinfunction "ETHRXN_W3") (pintype "bidirectional"))
    )
    (net (code "14") (name "ETH_TRF") (class "Default")
      (node (ref "J5") (pin "P9") (pinfunction "A_P9") (pintype "bidirectional"))
      (node (ref "U2") (pin "W7") (pinfunction "ETHLED1_W7") (pintype "bidirectional"))
    )
    (net (code "15") (name "ETH_TX+") (class "Default")
      (node (ref "J5") (pin "P1") (pinfunction "TD+_P1") (pintype "bidirectional"))
      (node (ref "U2") (pin "W4") (pinfunction "ETHTXP_W4") (pintype "bidirectional"))
    )
    (net (code "16") (name "ETH_TX-") (class "Default")
      (node (ref "J5") (pin "P3") (pinfunction "TD-_P3") (pintype "bidirectional"))
      (node (ref "U2") (pin "W5") (pinfunction "ETHTXN_W5") (pintype "bidirectional"))
    )
    (net (code "17") (name "GND") (class "Default")
      (node (ref "C1") (pin "2") (pinfunction "2_2") (pintype "passive"))
      (node (ref "C10") (pin "-") (pinfunction "-_-") (pintype "passive"))
      (node (ref "C11") (pin "2") (pinfunction "2_2") (pintype "passive"))
      (node (ref "C12") (pin "2") (pinfunction "2_2") (pintype "passive"))
      (node (ref "C15") (pin "-") (pinfunction "-_-") (pintype "passive"))
      (node (ref "C17") (pin "2") (pinfunction "2_2") (pintype "passive"))
      (node (ref "C19") (pin "2") (pinfunction "2_2") (pintype "passive"))
      (node (ref "C2") (pin "2") (pinfunction "2_2") (pintype "passive"))
      (node (ref "C20") (pin "1") (pinfunction "1_1") (pintype "passive"))
      (node (ref "C22") (pin "-") (pinfunction "-_-") (pintype "passive"))
      (node (ref "C23") (pin "-") (pinfunction "-_-") (pintype "passive"))
      (node (ref "C25") (pin "-") (pinfunction "-_-") (pintype "passive"))
      (node (ref "C26") (pin "2") (pinfunction "2_2") (pintype "passive"))
      (node (ref "C27") (pin "2") (pinfunction "2_2") (pintype "passive"))
      (node (ref "C28") (pin "2") (pinfunction "2_2") (pintype "passive"))
      (node (ref "C29") (pin "2") (pinfunction "2_2") (pintype "passive"))
      (node (ref "C30") (pin "-") (pinfunction "-_-") (pintype "passive"))
      (node (ref "C31") (pin "-") (pinfunction "-_-") (pintype "passive"))
      (node (ref "C32") (pin "2") (pinfunction "2_2") (pintype "passive"))
      (node (ref "C33") (pin "2") (pinfunction "2_2") (pintype "passive"))
      (node (ref "C4") (pin "2") (pinfunction "2_2") (pintype "passive"))
      (node (ref "C5") (pin "2") (pinfunction "2_2") (pintype "passive"))
      (node (ref "C6") (pin "-") (pinfunction "-_-") (pintype "passive"))
      (node (ref "C7") (pin "2") (pinfunction "2_2") (pintype "passive"))
      (node (ref "C8") (pin "2") (pinfunction "2_2") (pintype "passive"))
      (node (ref "C9") (pin "2") (pinfunction "2_2") (pintype "passive"))
      (node (ref "D1") (pin "A") (pinfunction "A_A") (pintype "passive"))
      (node (ref "D2") (pin "A") (pinfunction "A_A") (pintype "passive"))
      (node (ref "J1") (pin "4") (pinfunction "S_4") (pintype "bidirectional"))
      (node (ref "J2") (pin "1") (pinfunction "S_1") (pintype "bidirectional"))
      (node (ref "J2") (pin "3") (pinfunction "S_3") (pintype "bidirectional"))
      (node (ref "J2") (pin "5") (pinfunction "S_5") (pintype "bidirectional"))
      (node (ref "J3") (pin "6") (pinfunction "GND_6") (pintype "power_in"))
      (node (ref "J4") (pin "1") (pinfunction "S_1") (pintype "bidirectional"))
      (node (ref "J5") (pin "P10") (pinfunction "K_P10") (pintype "bidirectional"))
      (node (ref "J5") (pin "P12") (pinfunction "K_P12") (pintype "bidirectional"))
      (node (ref "J5") (pin "P8") (pinfunction "GND_P8") (pintype "bidirectional"))
      (node (ref "J7") (pin "6") (pinfunction "S_6") (pintype "bidirectional"))
      (node (ref "J9") (pin "3") (pinfunction "S_3") (pintype "bidirectional"))
      (node (ref "L2") (pin "1") (pinfunction "1_1") (pintype "passive"))
      (node (ref "L3") (pin "OA") (pinfunction "OA_OA") (pintype "passive"))
      (node (ref "R11") (pin "1") (pinfunction "1_1") (pintype "passive"))
      (node (ref "R12") (pin "1") (pinfunction "1_1") (pintype "passive"))
      (node (ref "R19") (pin "1") (pinfunction "1_1") (pintype "passive"))
      (node (ref "R21") (pin "1") (pinfunction "1_1") (pintype "passive"))
      (node (ref "R26") (pin "1") (pinfunction "1_1") (pintype "passive"))
      (node (ref "TP2") (pin "1") (pinfunction "P$1_1") (pintype "bidirectional"))
      (node (ref "U1") (pin "6") (pinfunction "GND_6") (pintype "bidirectional"))
      (node (ref "U2") (pin "E1") (pinfunction "GND_E1") (pintype "power_in"))
      (node (ref "U2") (pin "E14") (pinfunction "GND_E14") (pintype "power_in"))
      (node (ref "U2") (pin "E17") (pinfunction "GND_E17") (pintype "power_in"))
      (node (ref "U2") (pin "GND@1") (pinfunction "GND_GND@1") (pintype "power_in"))
      (node (ref "U2") (pin "GND@2") (pinfunction "GND_GND@2") (pintype "power_in"))
      (node (ref "U2") (pin "GND@3") (pinfunction "GND_GND@3") (pintype "power_in"))
      (node (ref "U2") (pin "GND@4") (pinfunction "GND_GND@4") (pintype "power_in"))
      (node (ref "U2") (pin "N24") (pinfunction "GND_N24") (pintype "power_in"))
      (node (ref "U2") (pin "S24") (pinfunction "GND_S24") (pintype "power_in"))
      (node (ref "U2") (pin "W1") (pinfunction "GND_W1") (pintype "power_in"))
      (node (ref "U3") (pin "11") (pinfunction "ZGND_11") (pintype "bidirectional"))
      (node (ref "U3") (pin "12") (pinfunction "AGNDL_12") (pintype "bidirectional"))
      (node (ref "U3") (pin "17") (pinfunction "AGNDR_17") (pintype "bidirectional"))
      (node (ref "U3") (pin "19") (pinfunction "PGND_19") (pintype "bidirectional"))
      (node (ref "U3") (pin "6") (pinfunction "DGND_6") (pintype "bidirectional"))
      (node (ref "U4") (pin "7") (pinfunction "GND_7") (pintype "bidirectional"))
      (node (ref "U4") (pin "T") (pinfunction "TP_T") (pintype "bidirectional"))
      (node (ref "U5") (pin "7") (pinfunction "GND_7") (pintype "bidirectional"))
      (node (ref "U5") (pin "EP") (pinfunction "EPAD_EP") (pintype "bidirectional"))
      (node (ref "U6") (pin "7") (pinfunction "GND_7") (pintype "bidirectional"))
      (node (ref "U6") (pin "EP") (pinfunction "EPAD_EP") (pintype "bidirectional"))
      (node (ref "U7") (pin "2") (pinfunction "A_2") (pintype "passive"))
      (node (ref "U8") (pin "1") (pinfunction "GND_1") (pintype "power_in"))
      (node (ref "W4") (pin "1") (pinfunction "P$1_1") (pintype "bidirectional"))
    )
    (net (code "18") (name "HID0") (class "Default")
      (node (ref "J7") (pin "5") (pinfunction "S_5") (pintype "bidirectional"))
      (node (ref "U3") (pin "22") (pinfunction "HID0/MS_22") (pintype "bidirectional"))
    )
    (net (code "19") (name "HID1") (class "Default")
      (node (ref "J7") (pin "7") (pinfunction "S_7") (pintype "bidirectional"))
      (node (ref "U3") (pin "23") (pinfunction "HID1/MC_23") (pintype "bidirectional"))
    )
    (net (code "20") (name "HID2") (class "Default")
      (node (ref "J7") (pin "3") (pinfunction "S_3") (pintype "bidirectional"))
      (node (ref "U3") (pin "24") (pinfunction "HID2/MD_24") (pintype "bidirectional"))
    )
    (net (code "21") (name "MISO") (class "Default")
      (node (ref "J2") (pin "20") (pinfunction "S_20") (pintype "bidirectional"))
      (node (ref "U2") (pin "S9") (pinfunction "PA14/MISO_S9") (pintype "bidirectional"))
    )
    (net (code "22") (name "MOSI") (class "Default")
      (node (ref "J2") (pin "18") (pinfunction "S_18") (pintype "bidirectional"))
      (node (ref "U2") (pin "S10") (pinfunction "PA13/MOSI_S10") (pintype "bidirectional"))
    )
    (net (code "23") (name "NRST") (class "Default")
      (node (ref "R16") (pin "2") (pinfunction "2_2") (pintype "passive"))
      (node (ref "U2") (pin "E21") (pinfunction "NRST_E21") (pintype "input"))
    )
    (net (code "24") (name "Net-(C13-Pad-)") (class "Default")
      (node (ref "C13") (pin "-") (pinfunction "-_-") (pintype "passive"))
      (node (ref "C14") (pin "-") (pinfunction "-_-") (pintype "passive"))
      (node (ref "R19") (pin "2") (pinfunction "2_2") (pintype "passive"))
    )
    (net (code "25") (name "Net-(C14-Pad+)") (class "Default")
      (node (ref "C14") (pin "+") (pinfunction "+_+") (pintype "passive"))
      (node (ref "R18") (pin "1") (pinfunction "1_1") (pintype "passive"))
      (node (ref "R29") (pin "1") (pinfunction "1_1") (pintype "passive"))
    )
    (net (code "26") (name "Net-(C16-Pad2)") (class "Default")
      (node (ref "C16") (pin "2") (pinfunction "2_2") (pintype "passive"))
      (node (ref "R21") (pin "2") (pinfunction "2_2") (pintype "passive"))
    )
    (net (code "27") (name "Net-(C17-Pad1)") (class "Default")
      (node (ref "C17") (pin "1") (pinfunction "1_1") (pintype "passive"))
      (node (ref "R20") (pin "1") (pinfunction "1_1") (pintype "passive"))
      (node (ref "R30") (pin "1") (pinfunction "1_1") (pintype "passive"))
    )
    (net (code "28") (name "Net-(C27-Pad1)") (class "Default")
      (node (ref "C27") (pin "1") (pinfunction "1_1") (pintype "passive"))
      (node (ref "R22") (pin "1") (pinfunction "1_1") (pintype "passive"))
    )
    (net (code "29") (name "Net-(C28-Pad1)") (class "Default")
      (node (ref "C28") (pin "1") (pinfunction "1_1") (pintype "passive"))
      (node (ref "R23") (pin "1") (pinfunction "1_1") (pintype "passive"))
    )
    (net (code "30") (name "Net-(F1-Pad1)") (class "Default")
      (node (ref "F1") (pin "1") (pinfunction "1_1") (pintype "passive"))
      (node (ref "L3") (pin "OB") (pinfunction "OB_OB") (pintype "passive"))
    )
    (net (code "31") (name "Net-(J6-5V)") (class "Default")
      (node (ref "C3") (pin "1") (pinfunction "1_1") (pintype "passive"))
      (node (ref "DA1") (pin "4") (pinfunction "4_4") (pintype "passive"))
      (node (ref "J6") (pin "1") (pinfunction "5V_1") (pintype "bidirectional"))
      (node (ref "L1") (pin "2") (pinfunction "2_2") (pintype "passive"))
    )
    (net (code "32") (name "Net-(J6-D+)") (class "Default")
      (node (ref "DA1") (pin "2") (pinfunction "2_2") (pintype "passive"))
      (node (ref "J6") (pin "3") (pinfunction "D+_3") (pintype "bidirectional"))
      (node (ref "R10") (pin "2") (pinfunction "2_2") (pintype "passive"))
    )
    (net (code "33") (name "Net-(J6-D-)") (class "Default")
      (node (ref "DA1") (pin "3") (pinfunction "3_3") (pintype "passive"))
      (node (ref "J6") (pin "2") (pinfunction "D-_2") (pintype "bidirectional"))
      (node (ref "R9") (pin "2") (pinfunction "2_2") (pintype "passive"))
    )
    (net (code "34") (name "Net-(J6-GND)") (class "Default")
      (node (ref "C3") (pin "2") (pinfunction "2_2") (pintype "passive"))
      (node (ref "DA1") (pin "1") (pinfunction "1_1") (pintype "passive"))
      (node (ref "J6") (pin "4") (pinfunction "GND_4") (pintype "bidirectional"))
      (node (ref "L2") (pin "2") (pinfunction "2_2") (pintype "passive"))
    )
    (net (code "35") (name "Net-(J8-GND)") (class "Default")
      (node (ref "C18") (pin "2") (pinfunction "2_2") (pintype "passive"))
      (node (ref "J8") (pin "2") (pinfunction "GND_2") (pintype "bidirectional"))
      (node (ref "J8") (pin "3") (pinfunction "SW_3") (pintype "bidirectional"))
      (node (ref "L3") (pin "IA") (pinfunction "IA_IA") (pintype "passive"))
    )
    (net (code "36") (name "Net-(J8-V+)") (class "Default")
      (node (ref "C18") (pin "1") (pinfunction "1_1") (pintype "passive"))
      (node (ref "J8") (pin "1") (pinfunction "V+_1") (pintype "bidirectional"))
      (node (ref "L3") (pin "IB") (pinfunction "IB_IB") (pintype "passive"))
    )
    (net (code "37") (name "Net-(J9B-S)") (class "Default")
      (node (ref "J9") (pin "2") (pinfunction "S_2") (pintype "bidirectional"))
      (node (ref "R24") (pin "2") (pinfunction "2_2") (pintype "passive"))
    )
    (net (code "38") (name "Net-(TP1-P$1)") (class "Default")
      (node (ref "TP1") (pin "1") (pinfunction "P$1_1") (pintype "bidirectional"))
      (node (ref "U2") (pin "E20") (pinfunction "VBAT_E20") (pintype "power_in"))
    )
    (net (code "39") (name "Net-(U2-PA9{slash}DRXD)") (class "Default")
      (node (ref "U2") (pin "S14") (pinfunction "PA9/DRXD_S14") (pintype "bidirectional"))
      (node (ref "W2") (pin "1") (pinfunction "P$1_1") (pintype "bidirectional"))
    )
    (net (code "40") (name "Net-(U2-PA10{slash}DTXD)") (class "Default")
      (node (ref "U2") (pin "S13") (pinfunction "PA10/DTXD_S13") (pintype "bidirectional"))
      (node (ref "W3") (pin "1") (pinfunction "P$1_1") (pintype "bidirectional"))
    )
    (net (code "41") (name "Net-(U3-D+)") (class "Default")
      (node (ref "R2") (pin "2") (pinfunction "2_2") (pintype "passive"))
      (node (ref "U3") (pin "9") (pinfunction "D+_9") (pintype "bidirectional"))
    )
    (net (code "42") (name "Net-(U3-D-)") (class "Default")
      (node (ref "R1") (pin "2") (pinfunction "2_2") (pintype "passive"))
      (node (ref "U3") (pin "8") (pinfunction "D-_8") (pintype "bidirectional"))
    )
    (net (code "43") (name "Net-(U3-DT)") (class "Default")
      (node (ref "R14") (pin "2") (pinfunction "2_2") (pintype "passive"))
      (node (ref "U3") (pin "3") (pinfunction "DT_3") (pintype "bidirectional"))
    )
    (net (code "44") (name "Net-(U3-VCCL)") (class "Default")
      (node (ref "C11") (pin "1") (pinfunction "1_1") (pintype "passive"))
      (node (ref "U3") (pin "13") (pinfunction "VCCL_13") (pintype "bidirectional"))
    )
    (net (code "45") (name "Net-(U3-VCCP)") (class "Default")
      (node (ref "C7") (pin "1") (pinfunction "1_1") (pintype "passive"))
      (node (ref "U3") (pin "20") (pinfunction "VCCP_20") (pintype "bidirectional"))
    )
    (net (code "46") (name "Net-(U3-VCCR)") (class "Default")
      (node (ref "C8") (pin "1") (pinfunction "1_1") (pintype "passive"))
      (node (ref "U3") (pin "16") (pinfunction "VCCR_16") (pintype "bidirectional"))
    )
    (net (code "47") (name "Net-(U3-VCOM)") (class "Default")
      (node (ref "C6") (pin "+") (pinfunction "+_+") (pintype "passive"))
      (node (ref "U3") (pin "18") (pinfunction "VCOM_18") (pintype "bidirectional"))
    )
    (net (code "48") (name "Net-(U3-VOUTL)") (class "Default")
      (node (ref "C13") (pin "+") (pinfunction "+_+") (pintype "passive"))
      (node (ref "C16") (pin "1") (pinfunction "1_1") (pintype "passive"))
      (node (ref "U3") (pin "14") (pinfunction "VOUTL_14") (pintype "bidirectional"))
    )
    (net (code "49") (name "Net-(U3-VOUTR)") (class "Default")
      (node (ref "U3") (pin "15") (pinfunction "VOUTR_15") (pintype "bidirectional"))
      (node (ref "W1") (pin "1") (pinfunction "P$1_1") (pintype "bidirectional"))
    )
    (net (code "50") (name "Net-(U3-XTI)") (class "Default")
      (node (ref "C5") (pin "1") (pinfunction "1_1") (pintype "passive"))
      (node (ref "Q1") (pin "2") (pinfunction "2_2") (pintype "passive"))
      (node (ref "R13") (pin "2") (pinfunction "2_2") (pintype "passive"))
      (node (ref "U3") (pin "28") (pinfunction "XTI_28") (pintype "bidirectional"))
    )
    (net (code "51") (name "Net-(U3-XTO)") (class "Default")
      (node (ref "C4") (pin "1") (pinfunction "1_1") (pintype "passive"))
      (node (ref "Q1") (pin "1") (pinfunction "1_1") (pintype "passive"))
      (node (ref "R13") (pin "1") (pinfunction "1_1") (pintype "passive"))
      (node (ref "U3") (pin "1") (pinfunction "XTO_1") (pintype "bidirectional"))
    )
    (net (code "52") (name "Net-(U4-IN+)") (class "Default")
      (node (ref "R18") (pin "2") (pinfunction "2_2") (pintype "passive"))
      (node (ref "R29") (pin "2") (pinfunction "2_2") (pintype "passive"))
      (node (ref "U4") (pin "3") (pinfunction "IN+_3") (pintype "bidirectional"))
    )
    (net (code "53") (name "Net-(U4-IN-)") (class "Default")
      (node (ref "R20") (pin "2") (pinfunction "2_2") (pintype "passive"))
      (node (ref "R30") (pin "2") (pinfunction "2_2") (pintype "passive"))
      (node (ref "U4") (pin "4") (pinfunction "IN-_4") (pintype "bidirectional"))
    )
    (net (code "54") (name "Net-(U4-VO+)") (class "Default")
      (node (ref "L6") (pin "1") (pinfunction "1_1") (pintype "passive"))
      (node (ref "U4") (pin "5") (pinfunction "VO+_5") (pintype "bidirectional"))
    )
    (net (code "55") (name "Net-(U4-VO-)") (class "Default")
      (node (ref "L7") (pin "1") (pinfunction "1_1") (pintype "passive"))
      (node (ref "U4") (pin "8") (pinfunction "VO-_8") (pintype "bidirectional"))
    )
    (net (code "56") (name "Net-(U5-BST)") (class "Default")
      (node (ref "C21") (pin "1") (pinfunction "1_1") (pintype "passive"))
      (node (ref "U5") (pin "1") (pinfunction "BST_1") (pintype "bidirectional"))
    )
    (net (code "57") (name "Net-(U5-SW)") (class "Default")
      (node (ref "C21") (pin "2") (pinfunction "2_2") (pintype "passive"))
      (node (ref "D1") (pin "K") (pinfunction "K_K") (pintype "passive"))
      (node (ref "L4") (pin "1") (pinfunction "1_1") (pintype "passive"))
      (node (ref "R22") (pin "2") (pinfunction "2_2") (pintype "passive"))
      (node (ref "U5") (pin "8") (pinfunction "SW_8") (pintype "bidirectional"))
    )
    (net (code "58") (name "Net-(U6-BST)") (class "Default")
      (node (ref "C24") (pin "1") (pinfunction "1_1") (pintype "passive"))
      (node (ref "U6") (pin "1") (pinfunction "BST_1") (pintype "bidirectional"))
    )
    (net (code "59") (name "Net-(U6-SW)") (class "Default")
      (node (ref "C24") (pin "2") (pinfunction "2_2") (pintype "passive"))
      (node (ref "D2") (pin "K") (pinfunction "K_K") (pintype "passive"))
      (node (ref "L5") (pin "1") (pinfunction "1_1") (pintype "passive"))
      (node (ref "R23") (pin "2") (pinfunction "2_2") (pintype "passive"))
      (node (ref "U6") (pin "8") (pinfunction "SW_8") (pintype "bidirectional"))
    )
    (net (code "60") (name "Net-(U8-~{RST})") (class "Default")
      (node (ref "R16") (pin "1") (pinfunction "1_1") (pintype "passive"))
      (node (ref "U8") (pin "2") (pinfunction "~{RST}_2") (pintype "open_collector"))
    )
    (net (code "61") (name "PC18{slash}PWM0") (class "Default")
      (node (ref "J2") (pin "10") (pinfunction "S_10") (pintype "bidirectional"))
      (node (ref "U2") (pin "N20") (pinfunction "PC18/PWM0_N20") (pintype "bidirectional"))
    )
    (net (code "62") (name "PC19{slash}PWM1") (class "Default")
      (node (ref "J2") (pin "12") (pinfunction "S_12") (pintype "bidirectional"))
      (node (ref "U2") (pin "N21") (pinfunction "PC19/PWM1_N21") (pintype "bidirectional"))
    )
    (net (code "63") (name "PC22{slash}TXD3") (class "Default")
      (node (ref "J2") (pin "13") (pinfunction "S_13") (pintype "bidirectional"))
      (node (ref "U2") (pin "E2") (pinfunction "PC22/TXD3_E2") (pintype "bidirectional"))
    )
    (net (code "64") (name "PC23{slash}RXD3") (class "Default")
      (node (ref "J2") (pin "15") (pinfunction "S_15") (pintype "bidirectional"))
      (node (ref "U2") (pin "E3") (pinfunction "PC23/RXD3_E3") (pintype "bidirectional"))
    )
    (net (code "65") (name "PC24{slash}RTS3") (class "Default")
      (node (ref "J2") (pin "17") (pinfunction "S_17") (pintype "bidirectional"))
      (node (ref "U2") (pin "E4") (pinfunction "PC24/RTS3_E4") (pintype "bidirectional"))
    )
    (net (code "66") (name "PC25{slash}CTS3") (class "Default")
      (node (ref "J2") (pin "19") (pinfunction "S_19") (pintype "bidirectional"))
      (node (ref "U2") (pin "E5") (pinfunction "PC25/CTS3_E5") (pintype "bidirectional"))
    )
    (net (code "67") (name "SCL0") (class "Default")
      (node (ref "J2") (pin "8") (pinfunction "S_8") (pintype "bidirectional"))
      (node (ref "R4") (pin "2") (pinfunction "2_2") (pintype "passive"))
      (node (ref "U2") (pin "W18") (pinfunction "PA31/SCL0_W18") (pintype "bidirectional"))
    )
    (net (code "68") (name "SDA0") (class "Default")
      (node (ref "J2") (pin "6") (pinfunction "S_6") (pintype "bidirectional"))
      (node (ref "R3") (pin "2") (pinfunction "2_2") (pintype "passive"))
      (node (ref "U2") (pin "W17") (pinfunction "PA30/SDA0_W17") (pintype "bidirectional"))
    )
    (net (code "69") (name "SD_CLK") (class "Default")
      (node (ref "J3") (pin "5") (pinfunction "CLK_5") (pintype "input"))
      (node (ref "U2") (pin "S6") (pinfunction "PA17/SD_CK_S6") (pintype "bidirectional"))
    )
    (net (code "70") (name "SD_CMD") (class "Default")
      (node (ref "J3") (pin "3") (pinfunction "CMD_3") (pintype "input"))
      (node (ref "U2") (pin "S7") (pinfunction "PA16/SD_CDA_S7") (pintype "bidirectional"))
    )
    (net (code "71") (name "SD_DAT0") (class "Default")
      (node (ref "J3") (pin "7") (pinfunction "DAT0_7") (pintype "bidirectional"))
      (node (ref "U2") (pin "S8") (pinfunction "PA15/SD_DA0_S8") (pintype "bidirectional"))
    )
    (net (code "72") (name "SD_DAT1") (class "Default")
      (node (ref "J3") (pin "8") (pinfunction "DAT1_8") (pintype "bidirectional"))
      (node (ref "U2") (pin "S5") (pinfunction "PA18/SD_DA1_S5") (pintype "bidirectional"))
    )
    (net (code "73") (name "SD_DAT2") (class "Default")
      (node (ref "J3") (pin "1") (pinfunction "DAT2_1") (pintype "bidirectional"))
      (node (ref "U2") (pin "S4") (pinfunction "PA19/SD_DA2_S4") (pintype "bidirectional"))
    )
    (net (code "74") (name "SD_DAT3") (class "Default")
      (node (ref "J3") (pin "2") (pinfunction "CD/DAT3_2") (pintype "bidirectional"))
      (node (ref "U2") (pin "S3") (pinfunction "PA20/SD_DA3_S3") (pintype "bidirectional"))
    )
    (net (code "75") (name "SPCK") (class "Default")
      (node (ref "J2") (pin "16") (pinfunction "S_16") (pintype "bidirectional"))
      (node (ref "U2") (pin "S11") (pinfunction "PA12/SPCK_S11") (pintype "bidirectional"))
    )
    (net (code "76") (name "SPI_CS0") (class "Default")
      (node (ref "J2") (pin "14") (pinfunction "S_14") (pintype "bidirectional"))
      (node (ref "U2") (pin "S12") (pinfunction "PA11/NPCS0_S12") (pintype "bidirectional"))
    )
    (net (code "77") (name "SPK+") (class "Default")
      (node (ref "C33") (pin "1") (pinfunction "1_1") (pintype "passive"))
      (node (ref "J7") (pin "10") (pinfunction "S_10") (pintype "bidirectional"))
      (node (ref "L6") (pin "2") (pinfunction "2_2") (pintype "passive"))
    )
    (net (code "78") (name "SPK-") (class "Default")
      (node (ref "C32") (pin "1") (pinfunction "1_1") (pintype "passive"))
      (node (ref "J7") (pin "9") (pinfunction "S_9") (pintype "bidirectional"))
      (node (ref "L7") (pin "2") (pinfunction "2_2") (pintype "passive"))
    )
    (net (code "79") (name "USBA_5V") (class "Default")
      (node (ref "C1") (pin "1") (pinfunction "1_1") (pintype "passive"))
      (node (ref "C2") (pin "1") (pinfunction "1_1") (pintype "passive"))
      (node (ref "L1") (pin "1") (pinfunction "1_1") (pintype "passive"))
      (node (ref "U1") (pin "8") (pinfunction "OUT1_8") (pintype "power_in"))
    )
    (net (code "80") (name "USBA_D+") (class "Default")
      (node (ref "R10") (pin "1") (pinfunction "1_1") (pintype "passive"))
      (node (ref "R12") (pin "2") (pinfunction "2_2") (pintype "passive"))
      (node (ref "U2") (pin "E19") (pinfunction "USBAP_E19") (pintype "bidirectional"))
    )
    (net (code "81") (name "USBA_D-") (class "Default")
      (node (ref "R11") (pin "2") (pinfunction "2_2") (pintype "passive"))
      (node (ref "R9") (pin "1") (pinfunction "1_1") (pintype "passive"))
      (node (ref "U2") (pin "E18") (pinfunction "USBAN_E18") (pintype "bidirectional"))
    )
    (net (code "82") (name "USBB_5V") (class "Default")
      (node (ref "J1") (pin "1") (pinfunction "S_1") (pintype "bidirectional"))
      (node (ref "U1") (pin "5") (pinfunction "OUT2_5") (pintype "power_in"))
    )
    (net (code "83") (name "USBB_D+") (class "Default")
      (node (ref "R15") (pin "1") (pinfunction "1_1") (pintype "passive"))
      (node (ref "R2") (pin "1") (pinfunction "1_1") (pintype "passive"))
      (node (ref "U2") (pin "E16") (pinfunction "USBBP_E16") (pintype "bidirectional"))
    )
    (net (code "84") (name "USBB_D-") (class "Default")
      (node (ref "R1") (pin "1") (pinfunction "1_1") (pintype "passive"))
      (node (ref "U2") (pin "E15") (pinfunction "USBBN_E15") (pintype "bidirectional"))
    )
    (net (code "85") (name "USBC_D+") (class "Default")
      (node (ref "J1") (pin "3") (pinfunction "S_3") (pintype "bidirectional"))
      (node (ref "U2") (pin "E12") (pinfunction "USBCP_E12") (pintype "bidirectional"))
    )
    (net (code "86") (name "USBC_D-") (class "Default")
      (node (ref "J1") (pin "2") (pinfunction "S_2") (pintype "bidirectional"))
      (node (ref "U2") (pin "E13") (pinfunction "USBCN_E13") (pintype "bidirectional"))
    )
    (net (code "87") (name "USB_EN1") (class "Default")
      (node (ref "R8") (pin "1") (pinfunction "1_1") (pintype "passive"))
      (node (ref "U1") (pin "1") (pinfunction "~{EN1}_1") (pintype "input"))
      (node (ref "U2") (pin "W13") (pinfunction "PA26_W13") (pintype "bidirectional"))
    )
    (net (code "88") (name "USB_EN2") (class "Default")
      (node (ref "R6") (pin "1") (pinfunction "1_1") (pintype "passive"))
      (node (ref "U1") (pin "4") (pinfunction "~{EN2}_4") (pintype "input"))
      (node (ref "U2") (pin "W16") (pinfunction "PA29_W16") (pintype "bidirectional"))
    )
    (net (code "89") (name "USB_FLAG1") (class "Default")
      (node (ref "R7") (pin "1") (pinfunction "1_1") (pintype "passive"))
      (node (ref "U1") (pin "2") (pinfunction "FLAG1_2") (pintype "output"))
      (node (ref "U2") (pin "W14") (pinfunction "PA27_W14") (pintype "bidirectional"))
    )
    (net (code "90") (name "USB_FLAG2") (class "Default")
      (node (ref "R5") (pin "1") (pinfunction "1_1") (pintype "passive"))
      (node (ref "U1") (pin "3") (pinfunction "FLAG2_3") (pintype "output"))
      (node (ref "U2") (pin "W15") (pinfunction "PA28_W15") (pintype "bidirectional"))
    )
    (net (code "91") (name "VCC") (class "Default")
      (node (ref "C15") (pin "+") (pinfunction "+_+") (pintype "passive"))
      (node (ref "C22") (pin "+") (pinfunction "+_+") (pintype "passive"))
      (node (ref "J9") (pin "5") (pinfunction "S_5") (pintype "bidirectional"))
      (node (ref "U5") (pin "2") (pinfunction "VIN_2") (pintype "bidirectional"))
      (node (ref "U5") (pin "3") (pinfunction "EN_3") (pintype "bidirectional"))
      (node (ref "U6") (pin "2") (pinfunction "VIN_2") (pintype "bidirectional"))
      (node (ref "U6") (pin "3") (pinfunction "EN_3") (pintype "bidirectional"))
    )
    (net (code "92") (name "VREF") (class "Default")
      (node (ref "C26") (pin "1") (pinfunction "1_1") (pintype "passive"))
      (node (ref "R28") (pin "1") (pinfunction "1_1") (pintype "passive"))
      (node (ref "U2") (pin "W19") (pinfunction "ADVREF_W19") (pintype "bidirectional"))
      (node (ref "U7") (pin "1") (pinfunction "K_1") (pintype "passive"))
    )
    (net (code "93") (name "V_AUX_ON") (class "Default")
      (node (ref "J9") (pin "1") (pinfunction "S_1") (pintype "bidirectional"))
      (node (ref "U2") (pin "W9") (pinfunction "PA22_W9") (pintype "bidirectional"))
    )
    (net (code "94") (name "V_MAIN") (class "Default")
      (node (ref "C19") (pin "1") (pinfunction "1_1") (pintype "passive"))
      (node (ref "F1") (pin "2") (pinfunction "2_2") (pintype "passive"))
      (node (ref "J9") (pin "4") (pinfunction "S_4") (pintype "bidirectional"))
    )
    (net (code "95") (name "unconnected-(J3-PadDC)") (class "Default")
      (node (ref "J3") (pin "DC") (pinfunction "DC_DC") (pintype "passive"))
    )
    (net (code "96") (name "unconnected-(J3-PadDT)") (class "Default")
      (node (ref "J3") (pin "DT") (pinfunction "DT_DT") (pintype "bidirectional"))
    )
    (net (code "97") (name "unconnected-(J7C-S-Pad2)") (class "Default")
      (node (ref "J7") (pin "2") (pinfunction "S_2") (pintype "bidirectional"))
    )
    (net (code "98") (name "unconnected-(U2-PA0{slash}TXD0-PadS23)") (class "Default")
      (node (ref "U2") (pin "S23") (pinfunction "PA0/TXD0_S23") (pintype "bidirectional"))
    )
    (net (code "99") (name "unconnected-(U2-PA1{slash}RXD0-PadS22)") (class "Default")
      (node (ref "U2") (pin "S22") (pinfunction "PA1/RXD0_S22") (pintype "bidirectional"))
    )
    (net (code "100") (name "unconnected-(U2-PA2{slash}RTS0-PadS21)") (class "Default")
      (node (ref "U2") (pin "S21") (pinfunction "PA2/RTS0_S21") (pintype "bidirectional"))
    )
    (net (code "101") (name "unconnected-(U2-PA3{slash}CTS0-PadS20)") (class "Default")
      (node (ref "U2") (pin "S20") (pinfunction "PA3/CTS0_S20") (pintype "bidirectional"))
    )
    (net (code "102") (name "unconnected-(U2-PA4-PadS19)") (class "Default")
      (node (ref "U2") (pin "S19") (pinfunction "PA4_S19") (pintype "bidirectional"))
    )
    (net (code "103") (name "unconnected-(U2-PA5{slash}TXD1-PadS18)") (class "Default")
      (node (ref "U2") (pin "S18") (pinfunction "PA5/TXD1_S18") (pintype "bidirectional"))
    )
    (net (code "104") (name "unconnected-(U2-PA6{slash}RXD1-PadS17)") (class "Default")
      (node (ref "U2") (pin "S17") (pinfunction "PA6/RXD1_S17") (pintype "bidirectional"))
    )
    (net (code "105") (name "unconnected-(U2-PA7{slash}TXD2-PadS16)") (class "Default")
      (node (ref "U2") (pin "S16") (pinfunction "PA7/TXD2_S16") (pintype "bidirectional"))
    )
    (net (code "106") (name "unconnected-(U2-PA8{slash}RXD2-PadS15)") (class "Default")
      (node (ref "U2") (pin "S15") (pinfunction "PA8/RXD2_S15") (pintype "bidirectional"))
    )
    (net (code "107") (name "unconnected-(U2-PA21{slash}1WIRE-PadS2)") (class "Default")
      (node (ref "U2") (pin "S2") (pinfunction "PA21/1WIRE_S2") (pintype "bidirectional"))
    )
    (net (code "108") (name "unconnected-(U2-PA23-PadW10)") (class "Default")
      (node (ref "U2") (pin "W10") (pinfunction "PA23_W10") (pintype "bidirectional"))
    )
    (net (code "109") (name "unconnected-(U2-PA24-PadW11)") (class "Default")
      (node (ref "U2") (pin "W11") (pinfunction "PA24_W11") (pintype "bidirectional"))
    )
    (net (code "110") (name "unconnected-(U2-PA25-PadW12)") (class "Default")
      (node (ref "U2") (pin "W12") (pinfunction "PA25_W12") (pintype "bidirectional"))
    )
    (net (code "111") (name "unconnected-(U2-PB13{slash}AD2-PadW22)") (class "Default")
      (node (ref "U2") (pin "W22") (pinfunction "PB13/AD2_W22") (pintype "bidirectional"))
    )
    (net (code "112") (name "unconnected-(U2-PB14{slash}AD3-PadW23)") (class "Default")
      (node (ref "U2") (pin "W23") (pinfunction "PB14/AD3_W23") (pintype "bidirectional"))
    )
    (net (code "113") (name "unconnected-(U2-PC0{slash}SDA1-PadN2)") (class "Default")
      (node (ref "U2") (pin "N2") (pinfunction "PC0/SDA1_N2") (pintype "bidirectional"))
    )
    (net (code "114") (name "unconnected-(U2-PC1{slash}SCL1-PadN3)") (class "Default")
      (node (ref "U2") (pin "N3") (pinfunction "PC1/SCL1_N3") (pintype "bidirectional"))
    )
    (net (code "115") (name "unconnected-(U2-PC2-PadN4)") (class "Default")
      (node (ref "U2") (pin "N4") (pinfunction "PC2_N4") (pintype "bidirectional"))
    )
    (net (code "116") (name "unconnected-(U2-PC3-PadN5)") (class "Default")
      (node (ref "U2") (pin "N5") (pinfunction "PC3_N5") (pintype "bidirectional"))
    )
    (net (code "117") (name "unconnected-(U2-PC4-PadN6)") (class "Default")
      (node (ref "U2") (pin "N6") (pinfunction "PC4_N6") (pintype "bidirectional"))
    )
    (net (code "118") (name "unconnected-(U2-PC5-PadN7)") (class "Default")
      (node (ref "U2") (pin "N7") (pinfunction "PC5_N7") (pintype "bidirectional"))
    )
    (net (code "119") (name "unconnected-(U2-PC6-PadN8)") (class "Default")
      (node (ref "U2") (pin "N8") (pinfunction "PC6_N8") (pintype "bidirectional"))
    )
    (net (code "120") (name "unconnected-(U2-PC7-PadN9)") (class "Default")
      (node (ref "U2") (pin "N9") (pinfunction "PC7_N9") (pintype "bidirectional"))
    )
    (net (code "121") (name "unconnected-(U2-PC8{slash}UTXD0-PadN10)") (class "Default")
      (node (ref "U2") (pin "N10") (pinfunction "PC8/UTXD0_N10") (pintype "bidirectional"))
    )
    (net (code "122") (name "unconnected-(U2-PC9{slash}URXD0-PadN11)") (class "Default")
      (node (ref "U2") (pin "N11") (pinfunction "PC9/URXD0_N11") (pintype "bidirectional"))
    )
    (net (code "123") (name "unconnected-(U2-PC10-PadN12)") (class "Default")
      (node (ref "U2") (pin "N12") (pinfunction "PC10_N12") (pintype "bidirectional"))
    )
    (net (code "124") (name "unconnected-(U2-PC11-PadN13)") (class "Default")
      (node (ref "U2") (pin "N13") (pinfunction "PC11_N13") (pintype "bidirectional"))
    )
    (net (code "125") (name "unconnected-(U2-PC12-PadN14)") (class "Default")
      (node (ref "U2") (pin "N14") (pinfunction "PC12_N14") (pintype "bidirectional"))
    )
    (net (code "126") (name "unconnected-(U2-PC13-PadN15)") (class "Default")
      (node (ref "U2") (pin "N15") (pinfunction "PC13_N15") (pintype "bidirectional"))
    )
    (net (code "127") (name "unconnected-(U2-PC14-PadN16)") (class "Default")
      (node (ref "U2") (pin "N16") (pinfunction "PC14_N16") (pintype "bidirectional"))
    )
    (net (code "128") (name "unconnected-(U2-PC15-PadN17)") (class "Default")
      (node (ref "U2") (pin "N17") (pinfunction "PC15_N17") (pintype "bidirectional"))
    )
    (net (code "129") (name "unconnected-(U2-PC16{slash}UTXD1-PadN18)") (class "Default")
      (node (ref "U2") (pin "N18") (pinfunction "PC16/UTXD1_N18") (pintype "bidirectional"))
    )
    (net (code "130") (name "unconnected-(U2-PC17{slash}URXD1-PadN19)") (class "Default")
      (node (ref "U2") (pin "N19") (pinfunction "PC17/URXD1_N19") (pintype "bidirectional"))
    )
    (net (code "131") (name "unconnected-(U2-PC20{slash}PWM2-PadN22)") (class "Default")
      (node (ref "U2") (pin "N22") (pinfunction "PC20/PWM2_N22") (pintype "bidirectional"))
    )
    (net (code "132") (name "unconnected-(U2-PC21{slash}PWM3-PadN23)") (class "Default")
      (node (ref "U2") (pin "N23") (pinfunction "PC21/PWM3_N23") (pintype "bidirectional"))
    )
    (net (code "133") (name "unconnected-(U2-PC26-PadE6)") (class "Default")
      (node (ref "U2") (pin "E6") (pinfunction "PC26_E6") (pintype "bidirectional"))
    )
    (net (code "134") (name "unconnected-(U2-PC27{slash}RTS1-PadE7)") (class "Default")
      (node (ref "U2") (pin "E7") (pinfunction "PC27/RTS1_E7") (pintype "bidirectional"))
    )
    (net (code "135") (name "unconnected-(U2-PC28{slash}CTS1-PadE8)") (class "Default")
      (node (ref "U2") (pin "E8") (pinfunction "PC28/CTS1_E8") (pintype "bidirectional"))
    )
    (net (code "136") (name "unconnected-(U2-PC29-PadE9)") (class "Default")
      (node (ref "U2") (pin "E9") (pinfunction "PC29_E9") (pintype "bidirectional"))
    )
    (net (code "137") (name "unconnected-(U2-PC30-PadE10)") (class "Default")
      (node (ref "U2") (pin "E10") (pinfunction "PC30_E10") (pintype "bidirectional"))
    )
    (net (code "138") (name "unconnected-(U2-PC31-PadE11)") (class "Default")
      (node (ref "U2") (pin "E11") (pinfunction "PC31_E11") (pintype "bidirectional"))
    )
    (net (code "139") (name "unconnected-(U2-SHDN-PadE22)") (class "Default")
      (node (ref "U2") (pin "E22") (pinfunction "SHDN_E22") (pintype "bidirectional"))
    )
    (net (code "140") (name "unconnected-(U2-WKUP-PadE23)") (class "Default")
      (node (ref "U2") (pin "E23") (pinfunction "WKUP_E23") (pintype "bidirectional"))
    )
    (net (code "141") (name "unconnected-(U3-CK-Pad2)") (class "Default")
      (node (ref "U3") (pin "2") (pinfunction "CK_2") (pintype "bidirectional"))
    )
    (net (code "142") (name "unconnected-(U5-PGOOD-Pad4)") (class "Default")
      (node (ref "U5") (pin "4") (pinfunction "PGOOD_4") (pintype "bidirectional"))
    )
    (net (code "143") (name "unconnected-(U6-PGOOD-Pad4)") (class "Default")
      (node (ref "U6") (pin "4") (pinfunction "PGOOD_4") (pintype "bidirectional"))
    )
    (net (code "144") (name "unconnected-(U8-~{MR}-Pad3)") (class "Default")
      (node (ref "U8") (pin "3") (pinfunction "~{MR}_3") (pintype "input"))
    )
  )
)
